# BACKPMAN20_CPU.net
KiCad netlist of a schematic drawn in Altium Designer
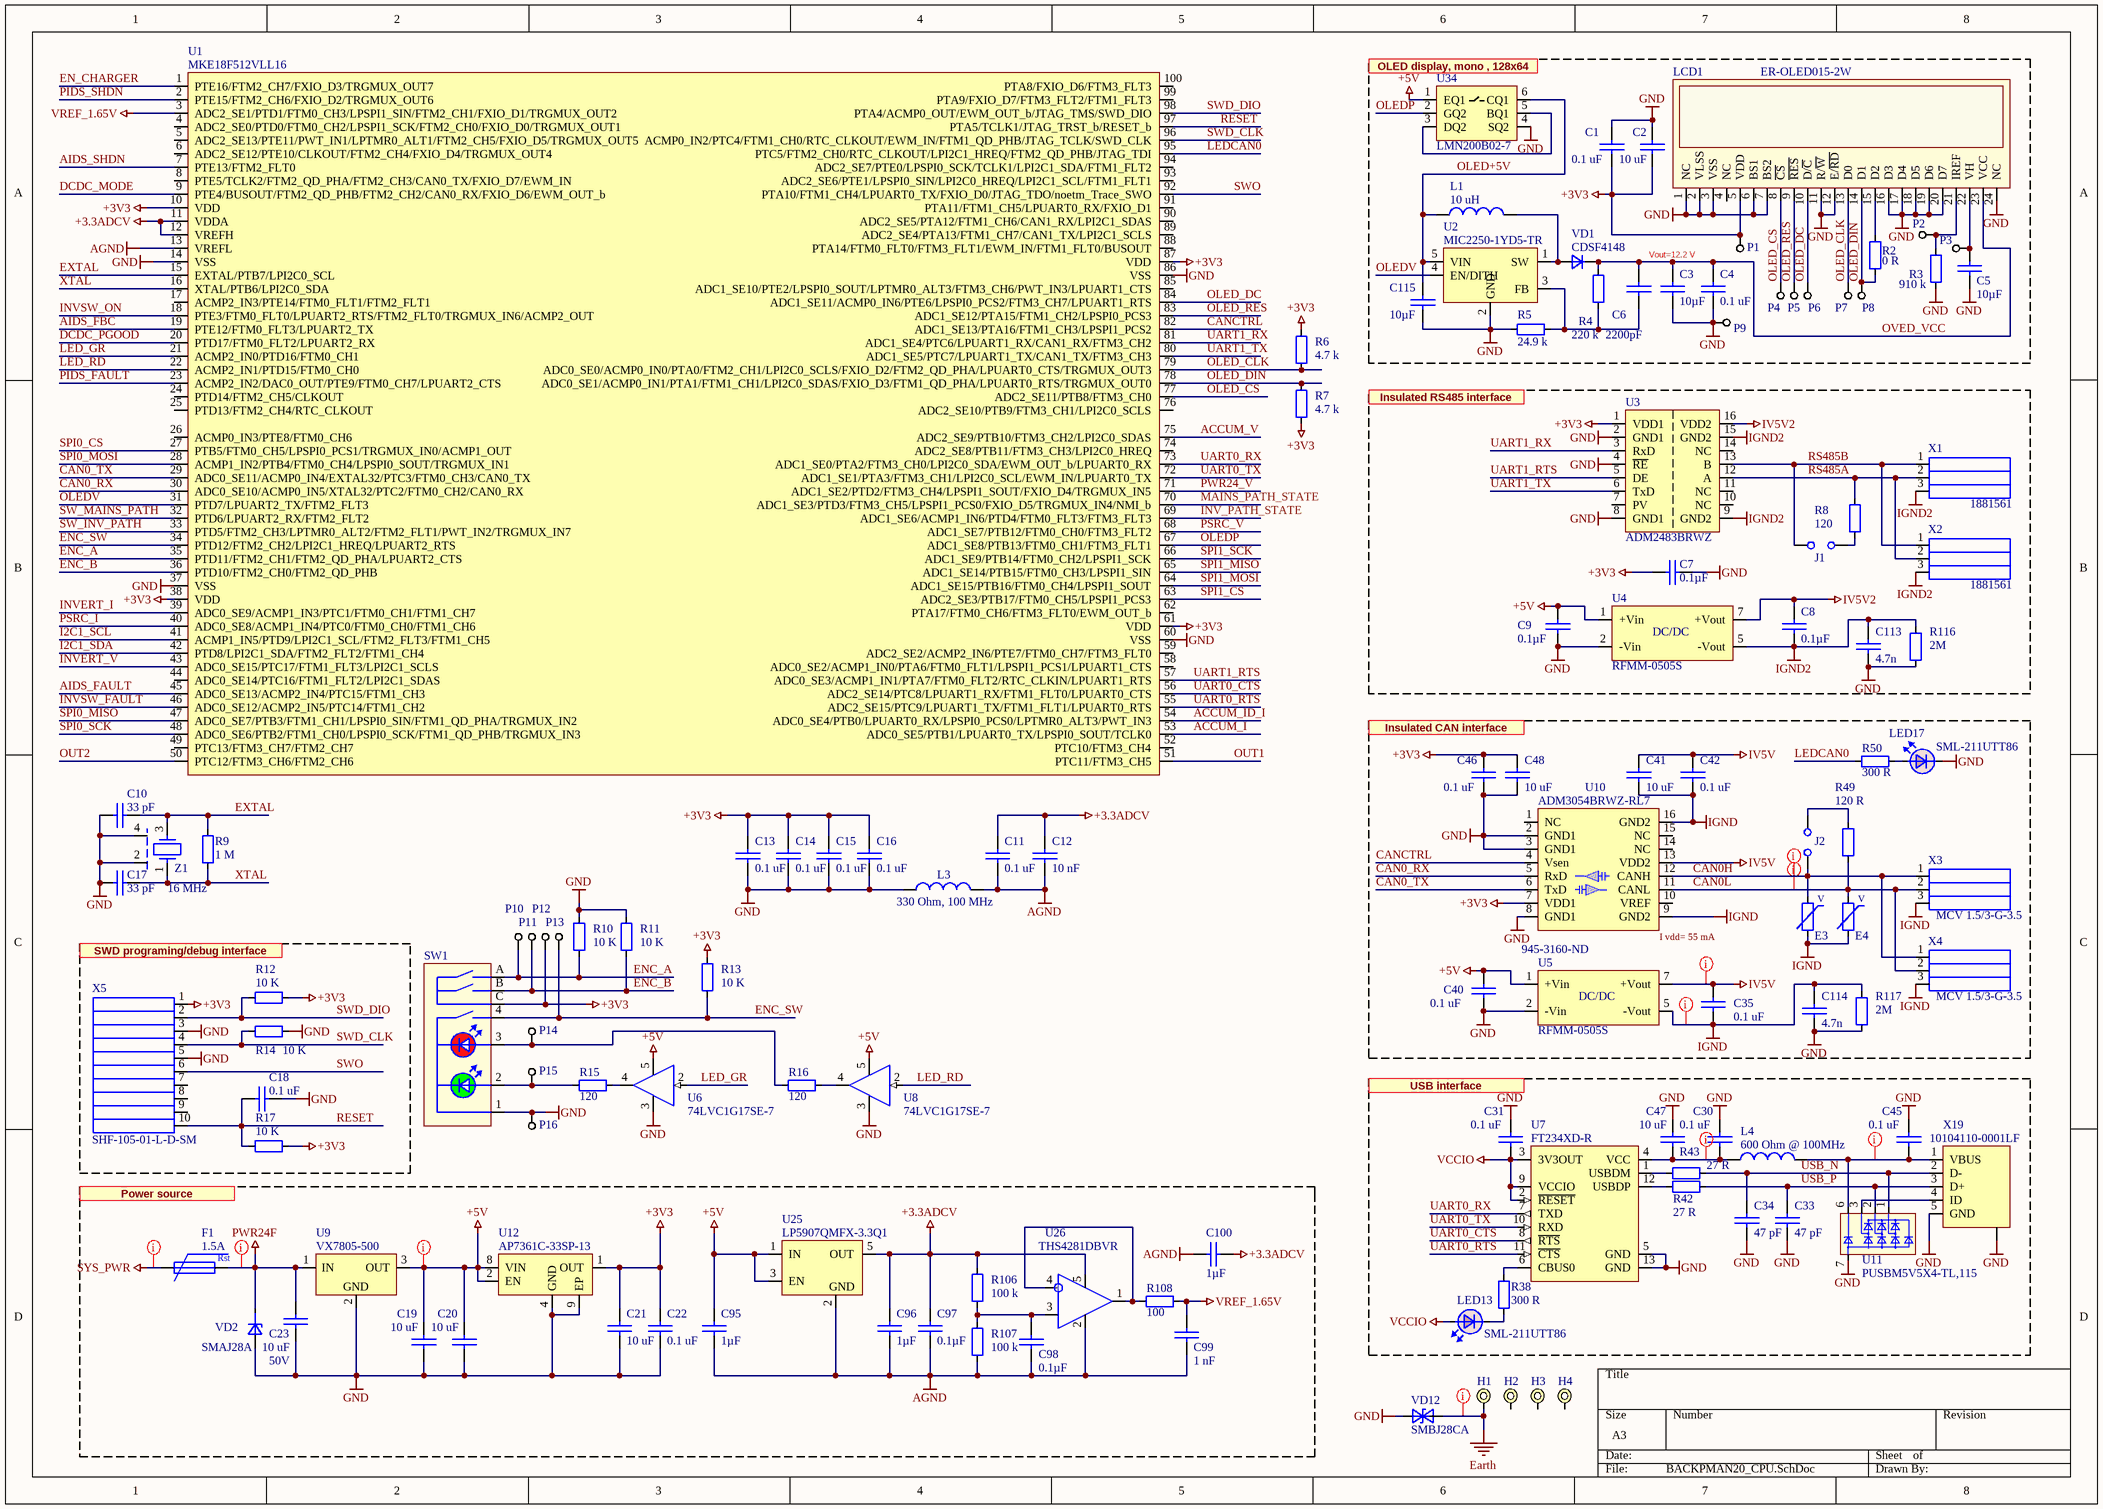
[diagram p0: BACKPMAN20_CPU.SchDoc]

(export (version "E")
  (design (tool "Eeschema 10.0.6"))
  (components
    (comp (ref "C1")
      (value "0.1 uF")
      (footprint "1608[0603]")
      (description "0.1 uF, 50V, 10% , X7R,  0603 SMD MLC Capacitor")
      (fields (field (name "TOLERANCE") "±10%") (field (name "MANUFACTURER") "WALSIN"))
      (libsource (lib "ea_Capacitors") (part "CVNF100K0603-25"))
    )
    (comp (ref "C2")
      (value "10 uF")
      (footprint "0805-1206")
      (description "CAP CER 10UF 10V 10% X5R 0805")
      (fields (field (name "MANUFACTURER") "Taiyo Yuden") (field (name "TOLERANCE") "10%"))
      (libsource (lib "ea_Capacitors") (part "LMK212F106ZG-T"))
    )
    (comp (ref "C3")
      (value "10µF")
      (footprint "0805 CAP")
      (description "10µF, ±10%, 25V, X5R, 0805 (2012 Metric), -55°C ~ 85°C, -, General Purpose")
      (fields (field (name "PART NUMBER") "TMK212BBJ106KG-T") (field (name "MANUFACTURER") "Taiyo Yuden"))
      (libsource (lib "ea_PassivComps") (part "Capacitor"))
    )
    (comp (ref "C4")
      (value "0.1 uF")
      (footprint "1608[0603]")
      (description "0.1 uF, 50V, 10% , X7R,  0603 SMD MLC Capacitor")
      (fields (field (name "TOLERANCE") "±10%") (field (name "MANUFACTURER") "WALSIN"))
      (libsource (lib "ea_Capacitors") (part "CVNF100K0603-25"))
    )
    (comp (ref "C5")
      (value "10µF")
      (footprint "0805 CAP")
      (description "10µF, ±10%, 25V, X5R, 0805 (2012 Metric), -55°C ~ 85°C, -, General Purpose")
      (fields (field (name "PART NUMBER") "TMK212BBJ106KG-T") (field (name "MANUFACTURER") "Taiyo Yuden"))
      (libsource (lib "ea_PassivComps") (part "Capacitor"))
    )
    (comp (ref "C6")
      (value "2200pF")
      (footprint "0603 CAP")
      (description "2200pF, ±10%, 25V, X7R, 0603 (1608 Metric), -55°C ~ 125°C, -, General Purpose")
      (fields (field (name "PART NUMBER") "CC0603KRX7R8BB222") (field (name "MANUFACTURER") "Yageo"))
      (libsource (lib "ea_PassivComps") (part "Capacitor"))
    )
    (comp (ref "C7")
      (value "0.1µF")
      (footprint "0603 CAP")
      (description "0.1µF, ±10%, 16V, X7R, 0603 (1608 Metric), -55°C ~ 125°C, -, General Purpose")
      (fields
        (field (name "PART NUMBER") "CL10B104KO8NNNC")
        (field (name "MANUFACTURER") "Samsung Electro-Mechanics")
      )
      (libsource (lib "ea_PassivComps") (part "Capacitor"))
    )
    (comp (ref "C8")
      (value "0.1µF")
      (footprint "0603 CAP")
      (description "0.1µF, ±10%, 16V, X7R, 0603 (1608 Metric), -55°C ~ 125°C, -, General Purpose")
      (fields
        (field (name "PART NUMBER") "CL10B104KO8NNNC")
        (field (name "MANUFACTURER") "Samsung Electro-Mechanics")
      )
      (libsource (lib "ea_PassivComps") (part "Capacitor"))
    )
    (comp (ref "C9")
      (value "0.1µF")
      (footprint "0603 CAP")
      (description "0.1µF, ±10%, 16V, X7R, 0603 (1608 Metric), -55°C ~ 125°C, -, General Purpose")
      (fields
        (field (name "PART NUMBER") "CL10B104KO8NNNC")
        (field (name "MANUFACTURER") "Samsung Electro-Mechanics")
      )
      (libsource (lib "ea_PassivComps") (part "Capacitor"))
    )
    (comp (ref "C10")
      (value "33 pF")
      (footprint "1005[0402]")
      (description "33 pF, 5%, 50V, C0G, NP0,  -55°C..125°C, 0402")
      (fields (field (name "TOLERANCE") "5%") (field (name "MANUFACTURER") "Kemet"))
      (libsource (lib "ea_Capacitors_0402") (part "CL05C330JB5NNNC"))
    )
    (comp (ref "C11")
      (value "0.1 uF")
      (footprint "1608[0603]")
      (description "0.1 uF, 50V, 10% , X7R,  0603 SMD MLC Capacitor")
      (fields (field (name "TOLERANCE") "±10%") (field (name "MANUFACTURER") "WALSIN"))
      (libsource (lib "ea_Capacitors") (part "CVNF100K0603-25"))
    )
    (comp (ref "C12")
      (value "10 nF")
      (footprint "1608[0603]")
      (description "10 nF, 50V, 10%, X7R, 0603 SMD MLC Capacitor")
      (fields (field (name "TOLERANCE") "±10%") (field (name "MANUFACTURER") "Murata Electronics"))
      (libsource (lib "ea_Capacitors") (part "CVNF010K0603"))
    )
    (comp (ref "C13")
      (value "0.1 uF")
      (footprint "1608[0603]")
      (description "0.1 uF, 50V, 10% , X7R,  0603 SMD MLC Capacitor")
      (fields (field (name "TOLERANCE") "±10%") (field (name "MANUFACTURER") "WALSIN"))
      (libsource (lib "ea_Capacitors") (part "CVNF100K0603-25"))
    )
    (comp (ref "C14")
      (value "0.1 uF")
      (footprint "1608[0603]")
      (description "0.1 uF, 50V, 10% , X7R,  0603 SMD MLC Capacitor")
      (fields (field (name "TOLERANCE") "±10%") (field (name "MANUFACTURER") "WALSIN"))
      (libsource (lib "ea_Capacitors") (part "CVNF100K0603-25"))
    )
    (comp (ref "C15")
      (value "0.1 uF")
      (footprint "1608[0603]")
      (description "0.1 uF, 50V, 10% , X7R,  0603 SMD MLC Capacitor")
      (fields (field (name "TOLERANCE") "±10%") (field (name "MANUFACTURER") "WALSIN"))
      (libsource (lib "ea_Capacitors") (part "CVNF100K0603-25"))
    )
    (comp (ref "C16")
      (value "0.1 uF")
      (footprint "1608[0603]")
      (description "0.1 uF, 50V, 10% , X7R,  0603 SMD MLC Capacitor")
      (fields (field (name "TOLERANCE") "±10%") (field (name "MANUFACTURER") "WALSIN"))
      (libsource (lib "ea_Capacitors") (part "CVNF100K0603-25"))
    )
    (comp (ref "C17")
      (value "33 pF")
      (footprint "1005[0402]")
      (description "33 pF, 5%, 50V, C0G, NP0,  -55°C..125°C, 0402")
      (fields (field (name "TOLERANCE") "5%") (field (name "MANUFACTURER") "Kemet"))
      (libsource (lib "ea_Capacitors_0402") (part "CL05C330JB5NNNC"))
    )
    (comp (ref "C18")
      (value "0.1 uF")
      (footprint "1608[0603]")
      (description "0.1 uF, 50V, 10% , X7R,  0603 SMD MLC Capacitor")
      (fields (field (name "TOLERANCE") "±10%") (field (name "MANUFACTURER") "WALSIN"))
      (libsource (lib "ea_Capacitors") (part "CVNF100K0603-25"))
    )
    (comp (ref "C19")
      (value "10 uF")
      (footprint "0805-1206")
      (description "CAP CER 10UF 10V 10% X5R 0805")
      (fields (field (name "MANUFACTURER") "Taiyo Yuden") (field (name "TOLERANCE") "10%"))
      (libsource (lib "ea_Capacitors") (part "LMK212F106ZG-T"))
    )
    (comp (ref "C20")
      (value "10 uF")
      (footprint "0805-1206")
      (description "CAP CER 10UF 10V 10% X5R 0805")
      (fields (field (name "MANUFACTURER") "Taiyo Yuden") (field (name "TOLERANCE") "10%"))
      (libsource (lib "ea_Capacitors") (part "LMK212F106ZG-T"))
    )
    (comp (ref "C21")
      (value "10 uF")
      (footprint "0805-1206")
      (description "CAP CER 10UF 10V 10% X5R 0805")
      (fields (field (name "MANUFACTURER") "Taiyo Yuden") (field (name "TOLERANCE") "10%"))
      (libsource (lib "ea_Capacitors") (part "LMK212F106ZG-T"))
    )
    (comp (ref "C22")
      (value "0.1 uF")
      (footprint "1608[0603]")
      (description "0.1 uF, 50V, 10% , X7R,  0603 SMD MLC Capacitor")
      (fields (field (name "TOLERANCE") "±10%") (field (name "MANUFACTURER") "WALSIN"))
      (libsource (lib "ea_Capacitors") (part "CVNF100K0603-25"))
    )
    (comp (ref "C23")
      (value "10 uF")
      (footprint "3225[1210]")
      (description "10uF, 50V, 20%, Y5V (F), 1210")
      (fields
        (field (name "MANUFACTURER") "Taiyo Yuden")
        (field (name "TOLERANCE") "20%")
        (field (name "VOLTAGE") "50V")
      )
      (libsource (lib "ea_Capacitors") (part "GRM32DF51H106ZA01L"))
    )
    (comp (ref "C30")
      (value "0.1 uF")
      (footprint "1608[0603]")
      (description "0.1 uF, 50V, 10% , X7R,  0603 SMD MLC Capacitor")
      (fields (field (name "TOLERANCE") "±10%") (field (name "MANUFACTURER") "WALSIN"))
      (libsource (lib "ea_Capacitors") (part "CVNF100K0603-25"))
    )
    (comp (ref "C31")
      (value "0.1 uF")
      (footprint "1608[0603]")
      (description "0.1 uF, 50V, 10% , X7R,  0603 SMD MLC Capacitor")
      (fields (field (name "TOLERANCE") "±10%") (field (name "MANUFACTURER") "WALSIN"))
      (libsource (lib "ea_Capacitors") (part "CVNF100K0603-25"))
    )
    (comp (ref "C33")
      (value "47 pF")
      (footprint "1608[0603]")
      (description "47 pF, 50V, 5%, NP0 SMD, -55°C ~ 150°C, 0603")
      (fields (field (name "MANUFACTURER") "TDK Corporation") (field (name "TOLERANCE") "5%"))
      (libsource (lib "ea_Capacitors_0603") (part "C1608NP01H470J080AA"))
    )
    (comp (ref "C34")
      (value "47 pF")
      (footprint "1608[0603]")
      (description "47 pF, 50V, 5%, NP0 SMD, -55°C ~ 150°C, 0603")
      (fields (field (name "MANUFACTURER") "TDK Corporation") (field (name "TOLERANCE") "5%"))
      (libsource (lib "ea_Capacitors_0603") (part "C1608NP01H470J080AA"))
    )
    (comp (ref "C35")
      (value "0.1 uF")
      (footprint "1608[0603]")
      (description "0.1 uF, 50V, 10% , X7R,  0603 SMD MLC Capacitor")
      (fields (field (name "TOLERANCE") "±10%") (field (name "MANUFACTURER") "WALSIN"))
      (libsource (lib "ea_Capacitors") (part "CVNF100K0603-25"))
    )
    (comp (ref "C40")
      (value "0.1 uF")
      (footprint "1608[0603]")
      (description "0.1 uF, 50V, 10% , X7R,  0603 SMD MLC Capacitor")
      (fields (field (name "TOLERANCE") "±10%") (field (name "MANUFACTURER") "WALSIN"))
      (libsource (lib "ea_Capacitors") (part "CVNF100K0603-25"))
    )
    (comp (ref "C41")
      (value "10 uF")
      (footprint "0805-1206")
      (description "CAP CER 10UF 10V 10% X5R 0805")
      (fields (field (name "MANUFACTURER") "Taiyo Yuden") (field (name "TOLERANCE") "10%"))
      (libsource (lib "ea_Capacitors") (part "LMK212F106ZG-T"))
    )
    (comp (ref "C42")
      (value "0.1 uF")
      (footprint "1608[0603]")
      (description "0.1 uF, 50V, 10% , X7R,  0603 SMD MLC Capacitor")
      (fields (field (name "TOLERANCE") "±10%") (field (name "MANUFACTURER") "WALSIN"))
      (libsource (lib "ea_Capacitors") (part "CVNF100K0603-25"))
    )
    (comp (ref "C45")
      (value "0.1 uF")
      (footprint "1608[0603]")
      (description "0.1 uF, 50V, 10% , X7R,  0603 SMD MLC Capacitor")
      (fields (field (name "TOLERANCE") "±10%") (field (name "MANUFACTURER") "WALSIN"))
      (libsource (lib "ea_Capacitors") (part "CVNF100K0603-25"))
    )
    (comp (ref "C46")
      (value "0.1 uF")
      (footprint "1608[0603]")
      (description "0.1 uF, 50V, 10% , X7R,  0603 SMD MLC Capacitor")
      (fields (field (name "TOLERANCE") "±10%") (field (name "MANUFACTURER") "WALSIN"))
      (libsource (lib "ea_Capacitors") (part "CVNF100K0603-25"))
    )
    (comp (ref "C47")
      (value "10 uF")
      (footprint "0805-1206")
      (description "10 uF, 6.3V, X5R, 10%, 0805")
      (fields (field (name "MANUFACTURER") "Murata") (field (name "TOLERANCE") "10%"))
      (libsource (lib "ea_Capacitors") (part "GRM21BR60J106KE19L"))
    )
    (comp (ref "C48")
      (value "10 uF")
      (footprint "0805-1206")
      (description "CAP CER 10UF 10V 10% X5R 0805")
      (fields (field (name "MANUFACTURER") "Taiyo Yuden") (field (name "TOLERANCE") "10%"))
      (libsource (lib "ea_Capacitors") (part "LMK212F106ZG-T"))
    )
    (comp (ref "C95")
      (value "1µF")
      (footprint "0603 CAP")
      (description "1µF, ±10%, 16V, X5R, 0603 (1608 Metric), -55°C ~ 85°C, -, General Purpose")
      (fields (field (name "PART NUMBER") "EMK107BJ105KA-T") (field (name "MANUFACTURER") "Taiyo Yuden"))
      (libsource (lib "ea_PassivComps") (part "Capacitor"))
    )
    (comp (ref "C96")
      (value "1µF")
      (footprint "0603 CAP")
      (description "1µF, ±10%, 16V, X5R, 0603 (1608 Metric), -55°C ~ 85°C, -, General Purpose")
      (fields (field (name "PART NUMBER") "EMK107BJ105KA-T") (field (name "MANUFACTURER") "Taiyo Yuden"))
      (libsource (lib "ea_PassivComps") (part "Capacitor"))
    )
    (comp (ref "C97")
      (value "0.1µF")
      (footprint "0603 CAP")
      (description "0.1µF, ±10%, 50V, X8L, 0603 (1608 Metric), -55°C ~ 150°C, -, Automotive")
      (fields
        (field (name "PART NUMBER") "GCM188L81H104KA57D")
        (field (name "MANUFACTURER") "Murata Electronics North America")
      )
      (libsource (lib "ea_PassivComps") (part "Capacitor"))
    )
    (comp (ref "C98")
      (value "0.1µF")
      (footprint "0603 CAP")
      (description "0.1µF, ±10%, 50V, X8L, 0603 (1608 Metric), -55°C ~ 150°C, -, Automotive")
      (fields
        (field (name "PART NUMBER") "GCM188L81H104KA57D")
        (field (name "MANUFACTURER") "Murata Electronics North America")
      )
      (libsource (lib "ea_PassivComps") (part "Capacitor"))
    )
    (comp (ref "C99")
      (value "1 nF")
      (footprint "0603 CAP")
      (description "1000pF, ±5%, 50V, X7R, 0603 (1608 Metric), -55°C ~ 125°C, -, General Purpose")
      (fields (field (name "PART NUMBER") "CC0603JRX7R9BB102") (field (name "MANUFACTURER") "Yageo"))
      (libsource (lib "ea_PassivComps") (part "Capacitor"))
    )
    (comp (ref "C100")
      (value "1µF")
      (footprint "0603 CAP")
      (description "1µF, ±10%, 16V, X5R, 0603 (1608 Metric), -55°C ~ 85°C, -, General Purpose")
      (fields (field (name "PART NUMBER") "EMK107BJ105KA-T") (field (name "MANUFACTURER") "Taiyo Yuden"))
      (libsource (lib "ea_PassivComps") (part "Capacitor"))
    )
    (comp (ref "C113")
      (value "4.7n")
      (footprint "0805 CAP")
      (description "4700pF ±10% 1000V (1kV) Ceramic Capacitor X7R 0805 (2012 Metric),-55°C ~ 125°C")
      (fields (field (name "MANUFACTURER") "KEMET") (field (name "TOLERANCE") "10%"))
      (libsource (lib "ea_Capacitors") (part "C0805V472KDRACTU"))
    )
    (comp (ref "C114")
      (value "4.7n")
      (footprint "0805 CAP")
      (description "4700pF ±10% 1000V (1kV) Ceramic Capacitor X7R 0805 (2012 Metric),-55°C ~ 125°C")
      (fields (field (name "MANUFACTURER") "KEMET") (field (name "TOLERANCE") "10%"))
      (libsource (lib "ea_Capacitors") (part "C0805V472KDRACTU"))
    )
    (comp (ref "C115")
      (value "10µF")
      (footprint "0805 CAP")
      (description "10µF, ±10%, 25V, X5R, 0805 (2012 Metric), -55°C ~ 85°C, -, General Purpose")
      (fields (field (name "PART NUMBER") "TMK212BBJ106KG-T") (field (name "MANUFACTURER") "Taiyo Yuden"))
      (libsource (lib "ea_PassivComps") (part "Capacitor"))
    )
    (comp (ref "E3")
      (value "823 560 505 60")
      (footprint "0603")
      (description "SUPPRESSOR ESD 5VDC, 56pF,  0603, -40..+85C")
      (fields (field (name "MANUFACTURER") "Würth Elektronik") (field (name "VOLTAGE") "5V"))
      (libsource (lib "ea_TVS_protection") (part "823 560 501 01"))
    )
    (comp (ref "E4")
      (value "823 560 505 60")
      (footprint "0603")
      (description "SUPPRESSOR ESD 5VDC, 56pF,  0603, -40..+85C")
      (fields (field (name "MANUFACTURER") "Würth Elektronik") (field (name "VOLTAGE") "5V"))
      (libsource (lib "ea_TVS_protection") (part "823 560 501 01"))
    )
    (comp (ref "F1")
      (value "1.5A")
      (footprint "2920 (7351 Metric)")
      (description "PTC RESETTABLE 60V 750MA, It=1.5A, 0.3s 2920(7351)")
      (fields (field (name "MANUFACTURER") "Bel Fuse Inc.") (field (name "PARTNUM") "507-1743-1-ND"))
      (libsource (lib "ea_Fuses") (part "0ZCF0075AF2C"))
    )
    (comp (ref "H1")
      (value "Hole 5MM Plated")
      (footprint "HOLE_5MM plated")
      (libsource (lib "ea_Mechanical") (part "Hole 5MM Plated"))
    )
    (comp (ref "H2")
      (value "Hole 5MM Plated")
      (footprint "HOLE_5MM plated")
      (libsource (lib "ea_Mechanical") (part "Hole 5MM Plated"))
    )
    (comp (ref "H3")
      (value "Hole 5MM Plated")
      (footprint "HOLE_5MM plated")
      (libsource (lib "ea_Mechanical") (part "Hole 5MM Plated"))
    )
    (comp (ref "H4")
      (value "Hole 5MM Plated")
      (footprint "HOLE_5MM plated")
      (libsource (lib "ea_Mechanical") (part "Hole 5MM Plated"))
    )
    (comp (ref "J1")
      (value "PH1-02-TA-HT")
      (footprint "HDR1X2V")
      (description "2 Pos. 2.54 mm Single Row Through Hole Straight Pin Header")
      (fields (field (name "MANUFACTURER") "ADAM TECH"))
      (libsource (lib "ea_Commutation") (part "Jumper"))
    )
    (comp (ref "J2")
      (value "PH1-02-TA-HT")
      (footprint "HDR1X2V")
      (description "2 Pos. 2.54 mm Single Row Through Hole Straight Pin Header")
      (fields (field (name "MANUFACTURER") "ADAM TECH"))
      (libsource (lib "ea_Commutation") (part "Jumper"))
    )
    (comp (ref "L1")
      (value "10 uH")
      (footprint "VLS4012ET")
      (description "10uH, 890 mA, 0.228 Ohm, +-20%,- 40 C to + 105 C")
      (fields (field (name "MANUFACTURER") "TDK Corporation") (field (name "PARTNUM") "445-6681-1-ND"))
      (libsource (lib "ea_Inductors") (part "VLS4012ET-100M"))
    )
    (comp (ref "L3")
      (value "330 Ohm, 100 MHz")
      (footprint "0603")
      (description "Ferrite bead, 330 Ohm, 100 MHz,  1.5 A, 0.07 Ohm")
      (fields
        (field (name "MANUFACTURER") "Murata Electronics North America")
        (field (name "PARTNUM") "BLM18SG331TN1D")
      )
      (libsource (lib "*") (part "BLM18SG331TN1D"))
    )
    (comp (ref "L4")
      (value "600 Ohm @ 100MHz")
      (footprint "0805")
      (description "FERRITE BEAD 600 OHM, 0805, -55°C ~ 125°C")
      (fields (field (name "MANUFACTURER") "TDK Corporation") (field (name "PARTNUM") "445-2206-1-ND"))
      (libsource (lib "ea_Inductors") (part "MPZ2012S601AT000"))
    )
    (comp (ref "LCD1")
      (value "ER-OLED015-2W")
      (footprint "ER-OLED015-2")
      (description "1.5\"OLED Display Serial 128x64 Module,SSD1309,White on Black")
      (fields
        (field (name "MANUFACTURER") "Orient Display")
        (field (name "PARTNUM") "2544-AOM12864A0-1.54WW-ND")
      )
      (libsource (lib "ea_LCD") (part "ER-OLED015-2W"))
    )
    (comp (ref "LED13")
      (value "SML-211UTT86")
      (footprint "0805 LED")
      (description "0805 red LED, hibright, 2 mA, 1.8V, 130°")
      (fields (field (name "MANUFACTURER") "Rohm") (field (name "PARTNUM") "511-1292-1-ND"))
      (libsource (lib "ea_Indicators") (part "SML-211UTT86"))
    )
    (comp (ref "LED17")
      (value "SML-211UTT86")
      (footprint "0805 LED")
      (description "0805 red LED, hibright, 2 mA, 1.8V, 130°")
      (fields (field (name "MANUFACTURER") "Rohm") (field (name "PARTNUM") "511-1292-1-ND"))
      (libsource (lib "ea_Indicators") (part "SML-211UTT86"))
    )
    (comp (ref "P1")
      (value "Pin 0.9 mm")
      (footprint "Pin 0.9 mm")
      (libsource (lib "ea_Contacts") (part "Pin 0.9 mm"))
    )
    (comp (ref "P2")
      (value "Pin 0.9 mm")
      (footprint "Pin 0.9 mm")
      (libsource (lib "ea_Contacts") (part "Pin 0.9 mm"))
    )
    (comp (ref "P3")
      (value "Pin 0.9 mm")
      (footprint "Pin 0.9 mm")
      (libsource (lib "ea_Contacts") (part "Pin 0.9 mm"))
    )
    (comp (ref "P4")
      (value "Pin 0.9 mm")
      (footprint "Pin 0.9 mm")
      (libsource (lib "ea_Contacts") (part "Pin 0.9 mm"))
    )
    (comp (ref "P5")
      (value "Pin 0.9 mm")
      (footprint "Pin 0.9 mm")
      (libsource (lib "ea_Contacts") (part "Pin 0.9 mm"))
    )
    (comp (ref "P6")
      (value "Pin 0.9 mm")
      (footprint "Pin 0.9 mm")
      (libsource (lib "ea_Contacts") (part "Pin 0.9 mm"))
    )
    (comp (ref "P7")
      (value "Pin 0.9 mm")
      (footprint "Pin 0.9 mm")
      (libsource (lib "ea_Contacts") (part "Pin 0.9 mm"))
    )
    (comp (ref "P8")
      (value "Pin 0.9 mm")
      (footprint "Pin 0.9 mm")
      (libsource (lib "ea_Contacts") (part "Pin 0.9 mm"))
    )
    (comp (ref "P9")
      (value "Pin 0.9 mm")
      (footprint "Pin 0.9 mm")
      (libsource (lib "ea_Contacts") (part "Pin 0.9 mm"))
    )
    (comp (ref "P10")
      (value "Pin 0.9 mm")
      (footprint "Pin 0.9 mm")
      (libsource (lib "ea_Contacts") (part "Pin 0.9 mm"))
    )
    (comp (ref "P11")
      (value "Pin 0.9 mm")
      (footprint "Pin 0.9 mm")
      (libsource (lib "ea_Contacts") (part "Pin 0.9 mm"))
    )
    (comp (ref "P12")
      (value "Pin 0.9 mm")
      (footprint "Pin 0.9 mm")
      (libsource (lib "ea_Contacts") (part "Pin 0.9 mm"))
    )
    (comp (ref "P13")
      (value "Pin 0.9 mm")
      (footprint "Pin 0.9 mm")
      (libsource (lib "ea_Contacts") (part "Pin 0.9 mm"))
    )
    (comp (ref "P14")
      (value "Pin 0.9 mm")
      (footprint "Pin 0.9 mm")
      (libsource (lib "ea_Contacts") (part "Pin 0.9 mm"))
    )
    (comp (ref "P15")
      (value "Pin 0.9 mm")
      (footprint "Pin 0.9 mm")
      (libsource (lib "ea_Contacts") (part "Pin 0.9 mm"))
    )
    (comp (ref "P16")
      (value "Pin 0.9 mm")
      (footprint "Pin 0.9 mm")
      (libsource (lib "ea_Contacts") (part "Pin 0.9 mm"))
    )
    (comp (ref "R2")
      (value "0 R")
      (footprint "0603")
      (description "0 R, Jumper, 0603, SMD Resistor, -55°C ~ 155°C")
      (fields (field (name "MANUFACTURER") "Yageo") (field (name "VOLTAGE") "75 V"))
      (libsource (lib "ea_Resistors_0603") (part "RC0603FR-070RL"))
    )
    (comp (ref "R3")
      (value "910 k")
      (footprint "0603")
      (fields
        (field (name "MANUFACTURER") "Stackpole Electronics Inc.")
        (field (name "TOLERANCE") "±1%")
        (field (name "VOLTAGE") "75V")
      )
      (libsource (lib "") (part "Resistor_1"))
    )
    (comp (ref "R4")
      (value "220 k")
      (footprint "0603")
      (fields
        (field (name "MANUFACTURER") "Stackpole Electronics Inc.")
        (field (name "TOLERANCE") "±1%")
        (field (name "VOLTAGE") "75V")
      )
      (libsource (lib "") (part "Resistor_1"))
    )
    (comp (ref "R5")
      (value "24.9 k")
      (footprint "0603")
      (fields
        (field (name "MANUFACTURER") "Stackpole Electronics Inc.")
        (field (name "TOLERANCE") "±1%")
        (field (name "VOLTAGE") "75V")
      )
      (libsource (lib "ea_PassivComps") (part "Resistor"))
    )
    (comp (ref "R6")
      (value "4.7 k")
      (footprint "0603")
      (fields
        (field (name "MANUFACTURER") "Stackpole Electronics Inc.")
        (field (name "TOLERANCE") "±1%")
        (field (name "VOLTAGE") "75V")
      )
      (libsource (lib "") (part "Resistor_1"))
    )
    (comp (ref "R7")
      (value "4.7 k")
      (footprint "0603")
      (fields
        (field (name "MANUFACTURER") "Stackpole Electronics Inc.")
        (field (name "TOLERANCE") "±1%")
        (field (name "VOLTAGE") "75V")
      )
      (libsource (lib "") (part "Resistor_1"))
    )
    (comp (ref "R8")
      (value "120")
      (footprint "0603")
      (fields
        (field (name "MANUFACTURER") "Stackpole Electronics Inc.")
        (field (name "TOLERANCE") "±1%")
        (field (name "VOLTAGE") "75V")
      )
      (libsource (lib "") (part "Resistor_1"))
    )
    (comp (ref "R9")
      (value "1 M")
      (footprint "0402")
      (description "1 M,  ±1%, ±100ppm/°C, Thick Film, -55°C ~ 155°C, 0402")
      (fields (field (name "MANUFACTURER") "Yageo") (field (name "TOLERANCE") "1%"))
      (libsource (lib "ea_Resistors_0402") (part "RC0402FR-071ML"))
    )
    (comp (ref "R10")
      (value "10 K")
      (footprint "0603")
      (description "10 K, 1%, 0603, SMD Resistor, Taped")
      (fields (field (name "MANUFACTURER") "Vishay") (field (name "TOLERANCE") "1%"))
      (libsource (lib "ea_Resistors_0603") (part "RL0603K010-1"))
    )
    (comp (ref "R11")
      (value "10 K")
      (footprint "0603")
      (description "10 K, 1%, 0603, SMD Resistor, Taped")
      (fields (field (name "MANUFACTURER") "Vishay") (field (name "TOLERANCE") "1%"))
      (libsource (lib "ea_Resistors_0603") (part "RL0603K010-1"))
    )
    (comp (ref "R12")
      (value "10 K")
      (footprint "0603")
      (description "10 K, 1%, 0603, SMD Resistor, Taped")
      (fields (field (name "MANUFACTURER") "Vishay") (field (name "TOLERANCE") "1%"))
      (libsource (lib "") (part "RL0603K010-1_1"))
    )
    (comp (ref "R13")
      (value "10 K")
      (footprint "0603")
      (description "10 K, 1%, 0603, SMD Resistor, Taped")
      (fields (field (name "MANUFACTURER") "Vishay") (field (name "TOLERANCE") "1%"))
      (libsource (lib "ea_Resistors_0603") (part "RL0603K010-1"))
    )
    (comp (ref "R14")
      (value "10 K")
      (footprint "0603")
      (description "10 K, 1%, 0603, SMD Resistor, Taped")
      (fields (field (name "MANUFACTURER") "Vishay") (field (name "TOLERANCE") "1%"))
      (libsource (lib "") (part "RL0603K010-1_1"))
    )
    (comp (ref "R15")
      (value "120")
      (footprint "0603")
      (fields
        (field (name "MANUFACTURER") "Stackpole Electronics Inc.")
        (field (name "TOLERANCE") "±1%")
        (field (name "VOLTAGE") "75V")
      )
      (libsource (lib "ea_PassivComps") (part "Resistor"))
    )
    (comp (ref "R16")
      (value "120")
      (footprint "0603")
      (fields
        (field (name "MANUFACTURER") "Stackpole Electronics Inc.")
        (field (name "TOLERANCE") "±1%")
        (field (name "VOLTAGE") "75V")
      )
      (libsource (lib "ea_PassivComps") (part "Resistor"))
    )
    (comp (ref "R17")
      (value "10 K")
      (footprint "0603")
      (description "10 K, 1%, 0603, SMD Resistor, Taped")
      (fields (field (name "MANUFACTURER") "Vishay") (field (name "TOLERANCE") "1%"))
      (libsource (lib "") (part "RL0603K010-1_1"))
    )
    (comp (ref "R38")
      (value "300 R")
      (footprint "0603")
      (description "300 R, 1%, 0.1 W, 0603, SMD Resistor, Taped")
      (fields (field (name "MANUFACTURER") "Vishay/Dale") (field (name "TOLERANCE") "1%"))
      (libsource (lib "") (part "CRCW0603300RFKEA_1"))
    )
    (comp (ref "R42")
      (value "27 R")
      (footprint "0603")
      (description "27 R, 1%, 0603, SMD,  -55°C ~ 155°C")
      (fields (field (name "MANUFACTURER") "Yageo") (field (name "TOLERANCE") "1%"))
      (libsource (lib "ea_Resistors_0603") (part "RC0603FR-0727RL"))
    )
    (comp (ref "R43")
      (value "27 R")
      (footprint "0603")
      (description "27 R, 1%, 0603, SMD,  -55°C ~ 155°C")
      (fields (field (name "MANUFACTURER") "Yageo") (field (name "TOLERANCE") "1%"))
      (libsource (lib "ea_Resistors_0603") (part "RC0603FR-0727RL"))
    )
    (comp (ref "R49")
      (value "120 R")
      (footprint "0603")
      (description "120 R, 1%, 0603, SMD Resistor, Taped")
      (fields (field (name "MANUFACTURER") "Vishay") (field (name "TOLERANCE") "±1%"))
      (libsource (lib "ea_Resistors") (part "RL0603E120-1"))
    )
    (comp (ref "R50")
      (value "300 R")
      (footprint "0603")
      (description "300 R, 1%, 0.1 W, 0603, SMD Resistor, Taped")
      (fields (field (name "MANUFACTURER") "Vishay/Dale") (field (name "TOLERANCE") "1%"))
      (libsource (lib "ea_Resistors_0603") (part "CRCW0603300RFKEA"))
    )
    (comp (ref "R106")
      (value "100 k")
      (footprint "0603")
      (description "100 kOhms, ±0.1%, 0.1W, 1/10W, Thin Film, ±25ppm/°C, 0603 (1608 Metric), -55°C ~ 155°C, -")
      (fields (field (name "MANUFACTURER") "Yageo") (field (name "TOLERANCE") "±0.1%"))
      (libsource (lib "") (part "Resistor_1"))
    )
    (comp (ref "R107")
      (value "100 k")
      (footprint "0603")
      (description "100 kOhms, ±0.1%, 0.1W, 1/10W, Thin Film, ±25ppm/°C, 0603 (1608 Metric), -55°C ~ 155°C, -")
      (fields (field (name "MANUFACTURER") "Yageo") (field (name "TOLERANCE") "±0.1%"))
      (libsource (lib "") (part "Resistor_1"))
    )
    (comp (ref "R108")
      (value "100")
      (footprint "0603")
      (fields
        (field (name "MANUFACTURER") "Stackpole Electronics Inc.")
        (field (name "TOLERANCE") "±1%")
        (field (name "VOLTAGE") "75V")
      )
      (libsource (lib "ea_PassivComps") (part "Resistor"))
    )
    (comp (ref "R116")
      (value "2M")
      (footprint "1206")
      (description "2 MOhms ±1% 0.25W, 1/4W Chip Resistor 1206 (3216 Metric) High Voltage Thick Film,-55°C ~ 155°C")
      (fields (field (name "MANUFACTURER") "Vishay Dale") (field (name "TOLERANCE") "±1%"))
      (libsource (lib "ea_Resistors") (part "RCV12062M00FKEA"))
    )
    (comp (ref "R117")
      (value "2M")
      (footprint "1206")
      (description "2 MOhms ±1% 0.25W, 1/4W Chip Resistor 1206 (3216 Metric) High Voltage Thick Film,-55°C ~ 155°C")
      (fields (field (name "MANUFACTURER") "Vishay Dale") (field (name "TOLERANCE") "±1%"))
      (libsource (lib "ea_Resistors") (part "RCV12062M00FKEA"))
    )
    (comp (ref "SW1")
      (value "PEL12D-4225S-S2024")
      (footprint "PEL12D-4225S-S2024")
      (description "Rotary Encoder Mechanical 24 Quadrature (Incremental) Vertical")
      (fields (field (name "MANUFACTURER") "Bourns Inc.") (field (name "PARTNUM") "PEL12D-4225S-S2024-ND"))
      (libsource (lib "ea_Commutation") (part "PEL12D-4225S-S2024"))
    )
    (comp (ref "U1")
      (value "MKE18F512VLL16")
      (footprint "LQPF100")
      (fields (field (name "MANUFACTURER") "NXP USA Inc.") (field (name "PARTNUM") "MKE18F512VLL16-ND"))
      (libsource (lib "ea_IC_CPU") (part "MKE18F512VLL16"))
    )
    (comp (ref "U2")
      (value "MIC2250-1YD5-TR")
      (footprint "SOT23-5")
      (description "Boost DC/DC, 2.5..5.5 to 1.24..32V, 900vA, 2.5Mhz, SOT-23-5, -40..+125 C")
      (fields (field (name "PARTNUM") "576-3967-1-ND") (field (name "MANUFACTURER") "Microchip Technology"))
      (libsource (lib "ea_IC_Power_Reg_Ref_Sw") (part "MIC2250-1YD5-TR"))
    )
    (comp (ref "U3")
      (value "ADM2483BRWZ")
      (footprint "SO-G16/D10.4")
      (description "RS422, RS485 Digital Isolator 2500Vrms 3 Channel 500kbps 25kV/µs CMTI 16-SOIC, -40°C ~ 85°C")
      (fields (field (name "MANUFACTURER") "Analog Divices") (field (name "PARTNUM") "ADM2483BRWZ-ND"))
      (libsource (lib "ea_IC_Interfaces") (part "ADM2483BRWZ"))
    )
    (comp (ref "U4")
      (value "RFMM-0505S")
      (footprint "Recom 7-SIP module")
      (description "1W DC-DC Unregulated Single Output , 5V in, 5 V out,  200mA, 4 kV, -40°C ~ 85°C")
      (fields (field (name "MANUFACTURER") "Recom Power") (field (name "PARTNUM") "945-3160-ND"))
      (libsource (lib "ea_PowerSources") (part "RFMM-0505S"))
    )
    (comp (ref "U5")
      (value "RFMM-0505S")
      (footprint "Recom 7-SIP module")
      (description "1W DC-DC Unregulated Single Output , 5V in, 5 V out,  200mA, 4 kV, -40°C ~ 85°C")
      (fields
        (field (name "MANUFACTURER") "Recom Power")
        (field (name "PARTNUM") "945-3160-ND")
        (field (name "SUPPLIER PART NUMBER 1") "945-3160-ND")
      )
      (libsource (lib "ea_PowerSources") (part "RFMM-0505S"))
    )
    (comp (ref "U6")
      (value "74LVC1G17SE-7")
      (footprint "SOT-353 ON Semi")
      (description "IC SGL SCHMITT BUFFER SOT353")
      (fields
        (field (name "MANUFACTURER") "Diodes Incorporated")
        (field (name "PARTNUM") "74LVC1G17SE-7CT-ND")
      )
      (libsource (lib "ea_IC_Logic") (part "74LVC1G17SE-7"))
    )
    (comp (ref "U7")
      (value "FT234XD-R")
      (footprint "FTDI DFN-12")
      (description "USB Bridge, USB to UART USB 2.0 UART Interface 12-DFN (3x3)")
      (fields (field (name "MANUFACTURER") "FTDI") (field (name "PARTNUM") "768-1178-1-ND"))
      (libsource (lib "ea_IC_Interfaces") (part "FT234XD"))
    )
    (comp (ref "U8")
      (value "74LVC1G17SE-7")
      (footprint "SOT-353 ON Semi")
      (description "IC SGL SCHMITT BUFFER SOT353")
      (fields
        (field (name "MANUFACTURER") "Diodes Incorporated")
        (field (name "PARTNUM") "74LVC1G17SE-7CT-ND")
      )
      (libsource (lib "ea_IC_Logic") (part "74LVC1G17SE-7"))
    )
    (comp (ref "U9")
      (value "VX7805-500")
      (footprint "VX7805-500")
      (description "Linear Regulator Replacement DC DC Converter 1 Output 5V 500mA 6.5V - 36V Input")
      (fields (field (name "MANUFACTURER") "CUI Inc.") (field (name "PARTNUM") "102-4244-ND"))
      (libsource (lib "ea_IC_Power_Reg_Ref_Sw") (part "VX7805-500"))
    )
    (comp (ref "U10")
      (value "ADM3054BRWZ-RL7")
      (footprint "SO-G16/D10.4")
      (description "IC Isol TXRX CAN HS 16SOIC")
      (fields (field (name "MANUFACTURER") "Analog Divices") (field (name "PARTNUM") "ADM3054BRWZ-RL7CT-ND"))
      (libsource (lib "ea_IC_Interfaces") (part "ADM3054BRWZ-RL7"))
    )
    (comp (ref "U11")
      (value "PUSBM5V5X4-TL,115")
      (footprint "DFN1616-6")
      (description "TVS DIODE 5.5VWM 12VC 6HXSON")
      (fields (field (name "MANUFACTURER") "NXP Semiconductors") (field (name "PARTNUM") "568-10921-1-ND"))
      (libsource (lib "ea_TVS_protection") (part "PUSBM5V5X4-TL,115"))
    )
    (comp (ref "U12")
      (value "AP7361C-33SP-13")
      (footprint "SOIC-8 EDP")
      (description "LDO, 3.3 V, 1A, 0.36V@1A, Vin=6V max, -40..+85C, 8-SO-EP")
      (fields
        (field (name "PARTNUM") "AP7361C-33SP-13DICT-ND")
        (field (name "MANUFACTURER") "Diodes Incorporated")
      )
      (libsource (lib "ea_IC_Power_Reg_Ref_Sw") (part "AP7361C-33SP-13"))
    )
    (comp (ref "U25")
      (value "LP5907QMFX-3.3Q1")
      (footprint "SOT23-5")
      (description "LDO 3.3 V, 250 mA, Vin < 5.5V, Iq < 12uA, -40..+125 C, SOT23-5")
      (fields (field (name "MANUFACTURER") "Texas Instruments") (field (name "PARTNUM") "296-40365-1-ND"))
      (libsource (lib "ea_IC_Power_Reg_Ref_Sw") (part "LP5907QMFX-3.3Q1"))
    )
    (comp (ref "U26")
      (value "THS4281DBVR")
      (footprint "SOT23-5")
      (description "Voltage Feedback Amplifier 1 Circuit Rail-to-Rail SOT-23-5")
      (fields (field (name "MANUFACTURER") "Texas Instruments") (field (name "PARTNUM") "296-39224-1-ND"))
      (libsource (lib "ea_IC_OPAmps_AnComparators") (part "THS4281DBVR"))
    )
    (comp (ref "U34")
      (value "LMN200B02-7")
      (footprint "SOT363")
      (fields (field (name "MANUFACTURER") "Diodes Incorporated") (field (name "PARTNUM") "LMN200B02DICT-ND"))
      (libsource (lib "ea_IC_drivers") (part "LMN200B02-7"))
    )
    (comp (ref "VD1")
      (value "CDSF4148")
      (footprint "1005")
      (description "150 mA, 75V, 1005, 125 C")
      (fields (field (name "MANUFACTURER") "Comchip Technology") (field (name "PARTNUM") "641-1004-1-ND"))
      (libsource (lib "ea_Diodes") (part "CDSF4148"))
    )
    (comp (ref "VD2")
      (value "SMAJ28A")
      (footprint "SMA")
      (description "DIODE TVS 28V 400W UNI 5% SMD")
      (fields (field (name "MANUFACTURER") "Bourns Inc.") (field (name "PARTNUM") "SMAJ28ABCT-ND"))
      (libsource (lib "ea_TVS_protection") (part "SMAJ28A"))
    )
    (comp (ref "VD12")
      (value "SMBJ28CA")
      (footprint "DO-214AA_SMBJ BI")
      (description "TVS 600W 28V Bidirectional")
      (fields (field (name "MANUFACTURER") "Littelfuse") (field (name "PARTNUM") "SMBJ28CABCT-ND"))
      (libsource (lib "ea_TVS_protection") (part "SMBJ28CA"))
    )
    (comp (ref "X1")
      (value "1881561")
      (footprint "1881561")
      (description "Printed-circuit board connector - MCV 0,5/ 3-G-2,5 - 1881561")
      (fields (field (name "MANUFACTURER") "Phoenix Contact"))
      (libsource (lib "ea_Connectors_2.5_mm_pitch") (part "1881561"))
    )
    (comp (ref "X2")
      (value "1881561")
      (footprint "1881561")
      (description "Printed-circuit board connector - MCV 0,5/ 3-G-2,5 - 1881561")
      (fields (field (name "MANUFACTURER") "Phoenix Contact"))
      (libsource (lib "ea_Connectors_2.5_mm_pitch") (part "1881561"))
    )
    (comp (ref "X3")
      (value "MCV 1.5/3-G-3.5")
      (footprint "mcv1.5-3-g_3.5 green + MC 1,5 3-ST-3,5 - 1840379")
      (description "HEADER, VERTICAL, 3.5MM, 3WAY")
      (fields (field (name "MANUFACTURER") "PHOENIX CONTACT") (field (name "PARTNUM") "1843619"))
      (libsource (lib "ea_PhoenixContacts") (part "MCV 1.5/3-G-3.5"))
    )
    (comp (ref "X4")
      (value "MCV 1.5/3-G-3.5")
      (footprint "mcv1.5-3-g_3.5 green + MC 1,5 3-ST-3,5 - 1840379")
      (description "HEADER, VERTICAL, 3.5MM, 3WAY")
      (fields (field (name "MANUFACTURER") "PHOENIX CONTACT") (field (name "PARTNUM") "1843619"))
      (libsource (lib "ea_PhoenixContacts") (part "MCV 1.5/3-G-3.5"))
    )
    (comp (ref "X5")
      (value "SHF-105-01-L-D-SM")
      (footprint "SHF-105-01-L-D-SM")
      (description "10 Positions Header Connector 0.050\" (1.27mm) Surface Mount Gold")
      (fields (field (name "MANUFACTURER") "Samtec Inc."))
      (libsource (lib "ea_Connectors_1.27_mm_pitch") (part "SHF-105-01-L-D-SM"))
    )
    (comp (ref "X19")
      (value "10104110-0001LF")
      (footprint "FCI micro USB B receptacle SMD")
      (description "USB - micro B USB 2.0 Receptacle Connector 5 Position Surface Mount, Right Angle")
      (fields (field (name "MANUFACTURER") "Amphenol FCI") (field (name "PARTNUM") "609-4052-1-ND"))
      (libsource (lib "ea_Connectors_USB") (part "10104110-0001LF"))
    )
    (comp (ref "Z1")
      (value "16 MHz")
      (footprint "4-SMD 2.00mm x 1.60mm")
      (description "16 MHz, 9 pF, ±10ppm, 2.00mm x 1.60mm, -20°C ~ 70°C")
      (fields (field (name "MANUFACTURER") "Abracon LLC") (field (name "PARTNUM") "535-13598-1-ND"))
      (libsource (lib "ea_OSC_CLK_GEN") (part "ABM11-16.000MHZ-9-B1U-T"))
    )
  )
  (nets
    (net (code "1") (name "+3.3ADCV") (class "Default")
      (node (ref "C100") (pin "1") (pinfunction "1_1") (pintype "passive"))
      (node (ref "C11") (pin "2") (pinfunction "2_2") (pintype "passive"))
      (node (ref "C12") (pin "1") (pinfunction "1_1") (pintype "passive"))
      (node (ref "C96") (pin "2") (pinfunction "2_2") (pintype "passive"))
      (node (ref "C97") (pin "1") (pinfunction "1_1") (pintype "passive"))
      (node (ref "R106") (pin "2") (pinfunction "2_2") (pintype "passive"))
      (node (ref "U1") (pin "11") (pinfunction "VDDA_11") (pintype "power_in"))
      (node (ref "U1") (pin "12") (pinfunction "VREFH_12") (pintype "power_in"))
      (node (ref "U25") (pin "5") (pinfunction "OUT_5") (pintype "power_in"))
      (node (ref "U26") (pin "5") (pinfunction "V+_5") (pintype "power_in"))
    )
    (net (code "2") (name "+3V3") (class "Default")
      (node (ref "C1") (pin "2") (pinfunction "2_2") (pintype "passive"))
      (node (ref "C13") (pin "2") (pinfunction "2_2") (pintype "passive"))
      (node (ref "C14") (pin "2") (pinfunction "2_2") (pintype "passive"))
      (node (ref "C15") (pin "2") (pinfunction "2_2") (pintype "passive"))
      (node (ref "C16") (pin "2") (pinfunction "2_2") (pintype "passive"))
      (node (ref "C2") (pin "1") (pinfunction "1_1") (pintype "passive"))
      (node (ref "C21") (pin "2") (pinfunction "2_2") (pintype "passive"))
      (node (ref "C22") (pin "2") (pinfunction "2_2") (pintype "passive"))
      (node (ref "C46") (pin "2") (pinfunction "2_2") (pintype "passive"))
      (node (ref "C48") (pin "2") (pinfunction "2_2") (pintype "passive"))
      (node (ref "C7") (pin "1") (pinfunction "1_1") (pintype "passive"))
      (node (ref "LCD1") (pin "5") (pinfunction "VDD_5") (pintype "passive"))
      (node (ref "P1") (pin "1") (pinfunction "1_1") (pintype "passive"))
      (node (ref "P12") (pin "1") (pinfunction "1_1") (pintype "passive"))
      (node (ref "R12") (pin "2") (pinfunction "2_2") (pintype "passive"))
      (node (ref "R13") (pin "2") (pinfunction "2_2") (pintype "passive"))
      (node (ref "R17") (pin "2") (pinfunction "2_2") (pintype "passive"))
      (node (ref "R6") (pin "2") (pinfunction "2_2") (pintype "passive"))
      (node (ref "R7") (pin "1") (pinfunction "1_1") (pintype "passive"))
      (node (ref "SW1") (pin "C") (pinfunction "C_C") (pintype "passive"))
      (node (ref "U1") (pin "10") (pinfunction "VDD_10") (pintype "power_in"))
      (node (ref "U1") (pin "38") (pinfunction "VDD_38") (pintype "power_in"))
      (node (ref "U1") (pin "61") (pinfunction "VDD_61") (pintype "power_in"))
      (node (ref "U1") (pin "87") (pinfunction "VDD_87") (pintype "power_in"))
      (node (ref "U10") (pin "7") (pinfunction "VDD1_7") (pintype "passive"))
      (node (ref "U12") (pin "1") (pinfunction "OUT_1") (pintype "passive"))
      (node (ref "U3") (pin "1") (pinfunction "VDD1_1") (pintype "passive"))
      (node (ref "X5") (pin "1") (pinfunction "1_1") (pintype "passive"))
    )
    (net (code "3") (name "+5V") (class "Default")
      (node (ref "C19") (pin "2") (pinfunction "2_2") (pintype "passive"))
      (node (ref "C20") (pin "2") (pinfunction "2_2") (pintype "passive"))
      (node (ref "C40") (pin "2") (pinfunction "2_2") (pintype "passive"))
      (node (ref "C9") (pin "2") (pinfunction "2_2") (pintype "passive"))
      (node (ref "C95") (pin "2") (pinfunction "2_2") (pintype "passive"))
      (node (ref "U12") (pin "2") (pinfunction "EN_2") (pintype "passive"))
      (node (ref "U12") (pin "8") (pinfunction "VIN_8") (pintype "passive"))
      (node (ref "U25") (pin "1") (pinfunction "IN_1") (pintype "power_in"))
      (node (ref "U25") (pin "3") (pinfunction "EN_3") (pintype "power_in"))
      (node (ref "U34") (pin "1") (pinfunction "EQ1_1") (pintype "passive"))
      (node (ref "U4") (pin "1") (pinfunction "+Vin_1") (pintype "passive"))
      (node (ref "U5") (pin "1") (pinfunction "+Vin_1") (pintype "passive"))
      (node (ref "U6") (pin "5") (pinfunction "VCC_5") (pintype "power_in"))
      (node (ref "U8") (pin "5") (pinfunction "VCC_5") (pintype "power_in"))
      (node (ref "U9") (pin "3") (pinfunction "OUT_3") (pintype "power_in"))
    )
    (net (code "4") (name "/ACCUM_I") (class "Default")
      (node (ref "U1") (pin "53") (pinfunction "ADC0_SE5/PTB1/LPUART0_TX/LPSPI0_SOUT/TCLK0_53") (pintype "bidirectional"))
    )
    (net (code "5") (name "/ACCUM_ID_I") (class "Default")
      (node (ref "U1") (pin "54") (pinfunction "ADC0_SE4/PTB0/LPUART0_RX/LPSPI0_PCS0/LPTMR0_ALT3/PWT_IN3_54") (pintype "bidirectional"))
    )
    (net (code "6") (name "/ACCUM_V") (class "Default")
      (node (ref "U1") (pin "75") (pinfunction "ADC2_SE9/PTB10/FTM3_CH2/LPI2C0_SDAS_75") (pintype "bidirectional"))
    )
    (net (code "7") (name "/AIDS_FAULT") (class "Default")
      (node (ref "U1") (pin "45") (pinfunction "ADC0_SE13/ACMP2_IN4/PTC15/FTM1_CH3_45") (pintype "bidirectional"))
    )
    (net (code "8") (name "/AIDS_FBC") (class "Default")
      (node (ref "U1") (pin "19") (pinfunction "PTE12/FTM0_FLT3/LPUART2_TX_19") (pintype "bidirectional"))
    )
    (net (code "9") (name "/AIDS_SHDN") (class "Default")
      (node (ref "U1") (pin "7") (pinfunction "PTE13/FTM2_FLT0_7") (pintype "bidirectional"))
    )
    (net (code "10") (name "/CAN0H") (class "Default")
      (node (ref "E3") (pin "2") (pinfunction "2_2") (pintype "passive"))
      (node (ref "J2") (pin "2") (pinfunction "2_2") (pintype "passive"))
      (node (ref "U10") (pin "12") (pinfunction "CANH_12") (pintype "passive"))
      (node (ref "X3") (pin "1") (pinfunction "1_1") (pintype "passive"))
      (node (ref "X4") (pin "1") (pinfunction "1_1") (pintype "passive"))
    )
    (net (code "11") (name "/CAN0L") (class "Default")
      (node (ref "E4") (pin "2") (pinfunction "2_2") (pintype "passive"))
      (node (ref "R49") (pin "1") (pinfunction "1_1") (pintype "passive"))
      (node (ref "U10") (pin "11") (pinfunction "CANL_11") (pintype "passive"))
      (node (ref "X3") (pin "2") (pinfunction "2_2") (pintype "passive"))
      (node (ref "X4") (pin "2") (pinfunction "2_2") (pintype "passive"))
    )
    (net (code "12") (name "/CAN0_RX") (class "Default")
      (node (ref "U1") (pin "30") (pinfunction "ADC0_SE10/ACMP0_IN5/XTAL32/PTC2/FTM0_CH2/CAN0_RX_30") (pintype "bidirectional"))
      (node (ref "U10") (pin "5") (pinfunction "RxD_5") (pintype "passive"))
    )
    (net (code "13") (name "/CAN0_TX") (class "Default")
      (node (ref "U1") (pin "29") (pinfunction "ADC0_SE11/ACMP0_IN4/EXTAL32/PTC3/FTM0_CH3/CAN0_TX_29") (pintype "bidirectional"))
      (node (ref "U10") (pin "6") (pinfunction "TxD_6") (pintype "passive"))
    )
    (net (code "14") (name "/CANCTRL") (class "Default")
      (node (ref "U1") (pin "82") (pinfunction "ADC1_SE13/PTA16/FTM1_CH3/LPSPI1_PCS2_82") (pintype "bidirectional"))
      (node (ref "U10") (pin "4") (pinfunction "Vsen_4") (pintype "passive"))
    )
    (net (code "15") (name "/DCDC_MODE") (class "Default")
      (node (ref "U1") (pin "9") (pinfunction "PTE4/BUSOUT/FTM2_QD_PHB/FTM2_CH2/CAN0_RX/FXIO_D6/EWM_OUT_b_9") (pintype "bidirectional"))
    )
    (net (code "16") (name "/DCDC_PGOOD") (class "Default")
      (node (ref "U1") (pin "20") (pinfunction "PTD17/FTM0_FLT2/LPUART2_RX_20") (pintype "bidirectional"))
    )
    (net (code "17") (name "/ENC_A") (class "Default")
      (node (ref "P10") (pin "1") (pinfunction "1_1") (pintype "passive"))
      (node (ref "R10") (pin "1") (pinfunction "1_1") (pintype "passive"))
      (node (ref "SW1") (pin "A") (pinfunction "A_A") (pintype "passive"))
      (node (ref "U1") (pin "35") (pinfunction "PTD11/FTM2_CH1/FTM2_QD_PHA/LPUART2_CTS_35") (pintype "bidirectional"))
    )
    (net (code "18") (name "/ENC_B") (class "Default")
      (node (ref "P11") (pin "1") (pinfunction "1_1") (pintype "passive"))
      (node (ref "R11") (pin "1") (pinfunction "1_1") (pintype "passive"))
      (node (ref "SW1") (pin "B") (pinfunction "B_B") (pintype "passive"))
      (node (ref "U1") (pin "36") (pinfunction "PTD10/FTM2_CH0/FTM2_QD_PHB_36") (pintype "bidirectional"))
    )
    (net (code "19") (name "/ENC_SW") (class "Default")
      (node (ref "P13") (pin "1") (pinfunction "1_1") (pintype "passive"))
      (node (ref "R13") (pin "1") (pinfunction "1_1") (pintype "passive"))
      (node (ref "SW1") (pin "4") (pinfunction "4_4") (pintype "passive"))
      (node (ref "U1") (pin "34") (pinfunction "PTD12/FTM2_CH2/LPI2C1_HREQ/LPUART2_RTS_34") (pintype "bidirectional"))
    )
    (net (code "20") (name "/EN_CHARGER") (class "Default")
      (node (ref "U1") (pin "1") (pinfunction "PTE16/FTM2_CH7/FXIO_D3/TRGMUX_OUT7_1") (pintype "bidirectional"))
    )
    (net (code "21") (name "/EXTAL") (class "Default")
      (node (ref "C10") (pin "1") (pinfunction "1_1") (pintype "passive"))
      (node (ref "R9") (pin "1") (pinfunction "1_1") (pintype "passive"))
      (node (ref "U1") (pin "15") (pinfunction "EXTAL/PTB7/LPI2C0_SCL_15") (pintype "bidirectional"))
      (node (ref "Z1") (pin "3") (pinfunction "3_3") (pintype "passive"))
    )
    (net (code "22") (name "/I2C1_SCL") (class "Default")
      (node (ref "U1") (pin "41") (pinfunction "ACMP1_IN5/PTD9/LPI2C1_SCL/FTM2_FLT3/FTM1_CH5_41") (pintype "bidirectional"))
    )
    (net (code "23") (name "/I2C1_SDA") (class "Default")
      (node (ref "U1") (pin "42") (pinfunction "PTD8/LPI2C1_SDA/FTM2_FLT2/FTM1_CH4_42") (pintype "bidirectional"))
    )
    (net (code "24") (name "/INVERT_I") (class "Default")
      (node (ref "U1") (pin "39") (pinfunction "ADC0_SE9/ACMP1_IN3/PTC1/FTM0_CH1/FTM1_CH7_39") (pintype "bidirectional"))
    )
    (net (code "25") (name "/INVERT_V") (class "Default")
      (node (ref "U1") (pin "43") (pinfunction "ADC0_SE15/PTC17/FTM1_FLT3/LPI2C1_SCLS_43") (pintype "bidirectional"))
    )
    (net (code "26") (name "/INVSW_FAULT") (class "Default")
      (node (ref "U1") (pin "46") (pinfunction "ADC0_SE12/ACMP2_IN5/PTC14/FTM1_CH2_46") (pintype "bidirectional"))
    )
    (net (code "27") (name "/INVSW_ON") (class "Default")
      (node (ref "U1") (pin "18") (pinfunction "PTE3/FTM0_FLT0/LPUART2_RTS/FTM2_FLT0/TRGMUX_IN6/ACMP2_OUT_18") (pintype "bidirectional"))
    )
    (net (code "28") (name "/INV_PATH_STATE") (class "Default")
      (node (ref "U1") (pin "69") (pinfunction "ADC1_SE6/ACMP1_IN6/PTD4/FTM0_FLT3/FTM3_FLT3_69") (pintype "bidirectional"))
    )
    (net (code "29") (name "/LEDCAN0") (class "Default")
      (node (ref "R50") (pin "2") (pinfunction "2_2") (pintype "passive"))
      (node (ref "U1") (pin "95") (pinfunction "PTC5/FTM2_CH0/RTC_CLKOUT/LPI2C1_HREQ/FTM2_QD_PHB/JTAG_TDI_95") (pintype "bidirectional"))
    )
    (net (code "30") (name "/LED_GR") (class "Default")
      (node (ref "U1") (pin "21") (pinfunction "ACMP2_IN0/PTD16/FTM0_CH1_21") (pintype "bidirectional"))
      (node (ref "U6") (pin "2") (pinfunction "A_2") (pintype "input"))
    )
    (net (code "31") (name "/LED_RD") (class "Default")
      (node (ref "U1") (pin "22") (pinfunction "ACMP2_IN1/PTD15/FTM0_CH0_22") (pintype "bidirectional"))
      (node (ref "U8") (pin "2") (pinfunction "A_2") (pintype "input"))
    )
    (net (code "32") (name "/MAINS_PATH_STATE") (class "Default")
      (node (ref "U1") (pin "70") (pinfunction "ADC1_SE3/PTD3/FTM3_CH5/LPSPI1_PCS0/FXIO_D5/TRGMUX_IN4/NMI_b_70") (pintype "bidirectional"))
    )
    (net (code "33") (name "/OLED+5V") (class "Default")
      (node (ref "C115") (pin "1") (pinfunction "1_1") (pintype "passive"))
      (node (ref "L1") (pin "1") (pinfunction "1_1") (pintype "passive"))
      (node (ref "U2") (pin "5") (pinfunction "VIN_5") (pintype "passive"))
      (node (ref "U34") (pin "6") (pinfunction "CQ1_6") (pintype "passive"))
    )
    (net (code "34") (name "/OLEDP") (class "Default")
      (node (ref "U1") (pin "67") (pinfunction "ADC1_SE8/PTB13/FTM0_CH1/FTM3_FLT1_67") (pintype "bidirectional"))
      (node (ref "U34") (pin "2") (pinfunction "GQ2_2") (pintype "passive"))
    )
    (net (code "35") (name "/OLEDV") (class "Default")
      (node (ref "U1") (pin "31") (pinfunction "PTD7/LPUART2_TX/FTM2_FLT3_31") (pintype "bidirectional"))
      (node (ref "U2") (pin "4") (pinfunction "EN/DITH_4") (pintype "passive"))
    )
    (net (code "36") (name "/OLED_CLK") (class "Default")
      (node (ref "LCD1") (pin "13") (pinfunction "D0_13") (pintype "passive"))
      (node (ref "P7") (pin "1") (pinfunction "1_1") (pintype "passive"))
      (node (ref "R6") (pin "1") (pinfunction "1_1") (pintype "passive"))
      (node (ref "U1") (pin "79") (pinfunction "ADC0_SE0/ACMP0_IN0/PTA0/FTM2_CH1/LPI2C0_SCLS/FXIO_D2/FTM2_QD_PHA/LPUART0_CTS/TRGMUX_OUT3_79") (pintype "bidirectional"))
    )
    (net (code "37") (name "/OLED_CS") (class "Default")
      (node (ref "LCD1") (pin "8") (pinfunction "~{CS}_8") (pintype "passive"))
      (node (ref "P4") (pin "1") (pinfunction "1_1") (pintype "passive"))
      (node (ref "U1") (pin "77") (pinfunction "ADC2_SE11/PTB8/FTM3_CH0_77") (pintype "bidirectional"))
    )
    (net (code "38") (name "/OLED_DC") (class "Default")
      (node (ref "LCD1") (pin "10") (pinfunction "D/~{C}_10") (pintype "passive"))
      (node (ref "P6") (pin "1") (pinfunction "1_1") (pintype "passive"))
      (node (ref "U1") (pin "84") (pinfunction "ADC1_SE11/ACMP0_IN6/PTE6/LPSPI0_PCS2/FTM3_CH7/LPUART1_RTS_84") (pintype "bidirectional"))
    )
    (net (code "39") (name "/OLED_DIN") (class "Default")
      (node (ref "LCD1") (pin "14") (pinfunction "D1_14") (pintype "passive"))
      (node (ref "P8") (pin "1") (pinfunction "1_1") (pintype "passive"))
      (node (ref "R2") (pin "1") (pinfunction "1_1") (pintype "passive"))
      (node (ref "R7") (pin "2") (pinfunction "2_2") (pintype "passive"))
      (node (ref "U1") (pin "78") (pinfunction "ADC0_SE1/ACMP0_IN1/PTA1/FTM1_CH1/LPI2C0_SDAS/FXIO_D3/FTM1_QD_PHA/LPUART0_RTS/TRGMUX_OUT0_78") (pintype "bidirectional"))
    )
    (net (code "40") (name "/OLED_RES") (class "Default")
      (node (ref "LCD1") (pin "9") (pinfunction "~{RES}_9") (pintype "passive"))
      (node (ref "P5") (pin "1") (pinfunction "1_1") (pintype "passive"))
      (node (ref "U1") (pin "83") (pinfunction "ADC1_SE12/PTA15/FTM1_CH2/LPSPI0_PCS3_83") (pintype "bidirectional"))
    )
    (net (code "41") (name "/OUT1") (class "Default")
      (node (ref "U1") (pin "51") (pinfunction "PTC11/FTM3_CH5_51") (pintype "bidirectional"))
    )
    (net (code "42") (name "/OUT2") (class "Default")
      (node (ref "U1") (pin "50") (pinfunction "PTC12/FTM3_CH6/FTM2_CH6_50") (pintype "bidirectional"))
    )
    (net (code "43") (name "/OVED_VCC") (class "Default")
      (node (ref "C3") (pin "1") (pinfunction "1_1") (pintype "passive"))
      (node (ref "C4") (pin "2") (pinfunction "2_2") (pintype "passive"))
      (node (ref "C6") (pin "1") (pinfunction "1_1") (pintype "passive"))
      (node (ref "LCD1") (pin "23") (pinfunction "VCC_23") (pintype "passive"))
      (node (ref "R4") (pin "2") (pinfunction "2_2") (pintype "passive"))
      (node (ref "VD1") (pin "1") (pinfunction "1_1") (pintype "passive"))
    )
    (net (code "44") (name "/PIDS_FAULT") (class "Default")
      (node (ref "U1") (pin "23") (pinfunction "ACMP2_IN2/DAC0_OUT/PTE9/FTM0_CH7/LPUART2_CTS_23") (pintype "bidirectional"))
    )
    (net (code "45") (name "/PIDS_SHDN") (class "Default")
      (node (ref "U1") (pin "2") (pinfunction "PTE15/FTM2_CH6/FXIO_D2/TRGMUX_OUT6_2") (pintype "bidirectional"))
    )
    (net (code "46") (name "/PSRC_I") (class "Default")
      (node (ref "U1") (pin "40") (pinfunction "ADC0_SE8/ACMP1_IN4/PTC0/FTM0_CH0/FTM1_CH6_40") (pintype "bidirectional"))
    )
    (net (code "47") (name "/PSRC_V") (class "Default")
      (node (ref "U1") (pin "68") (pinfunction "ADC1_SE7/PTB12/FTM0_CH0/FTM3_FLT2_68") (pintype "bidirectional"))
    )
    (net (code "48") (name "/PWR24_V") (class "Default")
      (node (ref "U1") (pin "71") (pinfunction "ADC1_SE2/PTD2/FTM3_CH4/LPSPI1_SOUT/FXIO_D4/TRGMUX_IN5_71") (pintype "bidirectional"))
    )
    (net (code "49") (name "/RESET") (class "Default")
      (node (ref "C18") (pin "2") (pinfunction "2_2") (pintype "passive"))
      (node (ref "R17") (pin "1") (pinfunction "1_1") (pintype "passive"))
      (node (ref "U1") (pin "97") (pinfunction "PTA5/TCLK1/JTAG_TRST_b/RESET_b_97") (pintype "bidirectional"))
      (node (ref "X5") (pin "10") (pinfunction "10_10") (pintype "passive"))
    )
    (net (code "50") (name "/RS485A") (class "Default")
      (node (ref "R8") (pin "2") (pinfunction "2_2") (pintype "passive"))
      (node (ref "U3") (pin "12") (pinfunction "A_12") (pintype "passive"))
      (node (ref "X1") (pin "2") (pinfunction "2_2") (pintype "passive"))
      (node (ref "X2") (pin "2") (pinfunction "2_2") (pintype "passive"))
    )
    (net (code "51") (name "/RS485B") (class "Default")
      (node (ref "J1") (pin "1") (pinfunction "1_1") (pintype "passive"))
      (node (ref "U3") (pin "13") (pinfunction "B_13") (pintype "passive"))
      (node (ref "X1") (pin "1") (pinfunction "1_1") (pintype "passive"))
      (node (ref "X2") (pin "1") (pinfunction "1_1") (pintype "passive"))
    )
    (net (code "52") (name "/SPI0_CS") (class "Default")
      (node (ref "U1") (pin "27") (pinfunction "PTB5/FTM0_CH5/LPSPI0_PCS1/TRGMUX_IN0/ACMP1_OUT_27") (pintype "bidirectional"))
    )
    (net (code "53") (name "/SPI0_MISO") (class "Default")
      (node (ref "U1") (pin "47") (pinfunction "ADC0_SE7/PTB3/FTM1_CH1/LPSPI0_SIN/FTM1_QD_PHA/TRGMUX_IN2_47") (pintype "bidirectional"))
    )
    (net (code "54") (name "/SPI0_MOSI") (class "Default")
      (node (ref "U1") (pin "28") (pinfunction "ACMP1_IN2/PTB4/FTM0_CH4/LPSPI0_SOUT/TRGMUX_IN1_28") (pintype "bidirectional"))
    )
    (net (code "55") (name "/SPI0_SCK") (class "Default")
      (node (ref "U1") (pin "48") (pinfunction "ADC0_SE6/PTB2/FTM1_CH0/LPSPI0_SCK/FTM1_QD_PHB/TRGMUX_IN3_48") (pintype "bidirectional"))
    )
    (net (code "56") (name "/SPI1_CS") (class "Default")
      (node (ref "U1") (pin "63") (pinfunction "ADC2_SE3/PTB17/FTM0_CH5/LPSPI1_PCS3_63") (pintype "bidirectional"))
    )
    (net (code "57") (name "/SPI1_MISO") (class "Default")
      (node (ref "U1") (pin "65") (pinfunction "ADC1_SE14/PTB15/FTM0_CH3/LPSPI1_SIN_65") (pintype "bidirectional"))
    )
    (net (code "58") (name "/SPI1_MOSI") (class "Default")
      (node (ref "U1") (pin "64") (pinfunction "ADC1_SE15/PTB16/FTM0_CH4/LPSPI1_SOUT_64") (pintype "bidirectional"))
    )
    (net (code "59") (name "/SPI1_SCK") (class "Default")
      (node (ref "U1") (pin "66") (pinfunction "ADC1_SE9/PTB14/FTM0_CH2/LPSPI1_SCK_66") (pintype "bidirectional"))
    )
    (net (code "60") (name "/SWD_CLK") (class "Default")
      (node (ref "R14") (pin "1") (pinfunction "1_1") (pintype "passive"))
      (node (ref "U1") (pin "96") (pinfunction "ACMP0_IN2/PTC4/FTM1_CH0/RTC_CLKOUT/EWM_IN/FTM1_QD_PHB/JTAG_TCLK/SWD_CLK_96") (pintype "bidirectional"))
      (node (ref "X5") (pin "4") (pinfunction "4_4") (pintype "passive"))
    )
    (net (code "61") (name "/SWD_DIO") (class "Default")
      (node (ref "R12") (pin "1") (pinfunction "1_1") (pintype "passive"))
      (node (ref "U1") (pin "98") (pinfunction "PTA4/ACMP0_OUT/EWM_OUT_b/JTAG_TMS/SWD_DIO_98") (pintype "bidirectional"))
      (node (ref "X5") (pin "2") (pinfunction "2_2") (pintype "passive"))
    )
    (net (code "62") (name "/SWO") (class "Default")
      (node (ref "U1") (pin "92") (pinfunction "PTA10/FTM1_CH4/LPUART0_TX/FXIO_D0/JTAG_TDO/noetm_Trace_SWO_92") (pintype "bidirectional"))
      (node (ref "X5") (pin "6") (pinfunction "6_6") (pintype "passive"))
    )
    (net (code "63") (name "/SW_INV_PATH") (class "Default")
      (node (ref "U1") (pin "33") (pinfunction "PTD5/FTM2_CH3/LPTMR0_ALT2/FTM2_FLT1/PWT_IN2/TRGMUX_IN7_33") (pintype "bidirectional"))
    )
    (net (code "64") (name "/SW_MAINS_PATH") (class "Default")
      (node (ref "U1") (pin "32") (pinfunction "PTD6/LPUART2_RX/FTM2_FLT2_32") (pintype "bidirectional"))
    )
    (net (code "65") (name "/UART0_CTS") (class "Default")
      (node (ref "U1") (pin "56") (pinfunction "ADC2_SE14/PTC8/LPUART1_RX/FTM1_FLT0/LPUART0_CTS_56") (pintype "bidirectional"))
      (node (ref "U7") (pin "8") (pinfunction "~{RTS}_8") (pintype "output"))
    )
    (net (code "66") (name "/UART0_RTS") (class "Default")
      (node (ref "U1") (pin "55") (pinfunction "ADC2_SE15/PTC9/LPUART1_TX/FTM1_FLT1/LPUART0_RTS_55") (pintype "bidirectional"))
      (node (ref "U7") (pin "11") (pinfunction "~{CTS}_11") (pintype "input"))
    )
    (net (code "67") (name "/UART0_RX") (class "Default")
      (node (ref "U1") (pin "73") (pinfunction "ADC1_SE0/PTA2/FTM3_CH0/LPI2C0_SDA/EWM_OUT_b/LPUART0_RX_73") (pintype "bidirectional"))
      (node (ref "U7") (pin "7") (pinfunction "TXD_7") (pintype "output"))
    )
    (net (code "68") (name "/UART0_TX") (class "Default")
      (node (ref "U1") (pin "72") (pinfunction "ADC1_SE1/PTA3/FTM3_CH1/LPI2C0_SCL/EWM_IN/LPUART0_TX_72") (pintype "bidirectional"))
      (node (ref "U7") (pin "10") (pinfunction "RXD_10") (pintype "input"))
    )
    (net (code "69") (name "/UART1_RTS") (class "Default")
      (node (ref "U1") (pin "57") (pinfunction "ADC0_SE3/ACMP1_IN1/PTA7/FTM0_FLT2/RTC_CLKIN/LPUART1_RTS_57") (pintype "bidirectional"))
      (node (ref "U3") (pin "5") (pinfunction "DE_5") (pintype "passive"))
    )
    (net (code "70") (name "/UART1_RX") (class "Default")
      (node (ref "U1") (pin "81") (pinfunction "ADC1_SE4/PTC6/LPUART1_RX/CAN1_RX/FTM3_CH2_81") (pintype "bidirectional"))
      (node (ref "U3") (pin "3") (pinfunction "RxD_3") (pintype "passive"))
    )
    (net (code "71") (name "/UART1_TX") (class "Default")
      (node (ref "U1") (pin "80") (pinfunction "ADC1_SE5/PTC7/LPUART1_TX/CAN1_TX/FTM3_CH3_80") (pintype "bidirectional"))
      (node (ref "U3") (pin "6") (pinfunction "TxD_6") (pintype "passive"))
    )
    (net (code "72") (name "/USB_N") (class "Default")
      (node (ref "C34") (pin "1") (pinfunction "1_1") (pintype "passive"))
      (node (ref "R43") (pin "2") (pinfunction "2_2") (pintype "passive"))
      (node (ref "U11") (pin "1") (pinfunction "1_1") (pintype "passive"))
      (node (ref "X19") (pin "2") (pinfunction "D-_2") (pintype "bidirectional"))
    )
    (net (code "73") (name "/USB_P") (class "Default")
      (node (ref "C33") (pin "1") (pinfunction "1_1") (pintype "passive"))
      (node (ref "R42") (pin "2") (pinfunction "2_2") (pintype "passive"))
      (node (ref "U11") (pin "2") (pinfunction "2_2") (pintype "passive"))
      (node (ref "X19") (pin "3") (pinfunction "D+_3") (pintype "bidirectional"))
    )
    (net (code "74") (name "/XTAL") (class "Default")
      (node (ref "C17") (pin "1") (pinfunction "1_1") (pintype "passive"))
      (node (ref "R9") (pin "2") (pinfunction "2_2") (pintype "passive"))
      (node (ref "U1") (pin "16") (pinfunction "XTAL/PTB6/LPI2C0_SDA_16") (pintype "bidirectional"))
      (node (ref "Z1") (pin "1") (pinfunction "1_1") (pintype "passive"))
    )
    (net (code "75") (name "AGND") (class "Default")
      (node (ref "C100") (pin "2") (pinfunction "2_2") (pintype "passive"))
      (node (ref "C11") (pin "1") (pinfunction "1_1") (pintype "passive"))
      (node (ref "C12") (pin "2") (pinfunction "2_2") (pintype "passive"))
      (node (ref "C95") (pin "1") (pinfunction "1_1") (pintype "passive"))
      (node (ref "C96") (pin "1") (pinfunction "1_1") (pintype "passive"))
      (node (ref "C97") (pin "2") (pinfunction "2_2") (pintype "passive"))
      (node (ref "C98") (pin "2") (pinfunction "2_2") (pintype "passive"))
      (node (ref "C99") (pin "2") (pinfunction "2_2") (pintype "passive"))
      (node (ref "L3") (pin "2") (pinfunction "2_2") (pintype "passive"))
      (node (ref "R107") (pin "1") (pinfunction "1_1") (pintype "passive"))
      (node (ref "U1") (pin "13") (pinfunction "VREFL_13") (pintype "power_in"))
      (node (ref "U25") (pin "2") (pinfunction "GND_2") (pintype "power_in"))
      (node (ref "U26") (pin "2") (pinfunction "GND_2") (pintype "power_in"))
    )
    (net (code "76") (name "Earth") (class "Default")
      (node (ref "H1") (pin "0") (pinfunction "0_0") (pintype "passive"))
      (node (ref "VD12") (pin "2") (pinfunction "A_2") (pintype "passive"))
    )
    (net (code "77") (name "GND") (class "Default")
      (node (ref "C1") (pin "1") (pinfunction "1_1") (pintype "passive"))
      (node (ref "C10") (pin "2") (pinfunction "2_2") (pintype "passive"))
      (node (ref "C113") (pin "2") (pinfunction "2_2") (pintype "passive"))
      (node (ref "C114") (pin "2") (pinfunction "2_2") (pintype "passive"))
      (node (ref "C115") (pin "2") (pinfunction "2_2") (pintype "passive"))
      (node (ref "C13") (pin "1") (pinfunction "1_1") (pintype "passive"))
      (node (ref "C14") (pin "1") (pinfunction "1_1") (pintype "passive"))
      (node (ref "C15") (pin "1") (pinfunction "1_1") (pintype "passive"))
      (node (ref "C16") (pin "1") (pinfunction "1_1") (pintype "passive"))
      (node (ref "C17") (pin "2") (pinfunction "2_2") (pintype "passive"))
      (node (ref "C18") (pin "1") (pinfunction "1_1") (pintype "passive"))
      (node (ref "C19") (pin "1") (pinfunction "1_1") (pintype "passive"))
      (node (ref "C2") (pin "2") (pinfunction "2_2") (pintype "passive"))
      (node (ref "C20") (pin "1") (pinfunction "1_1") (pintype "passive"))
      (node (ref "C21") (pin "1") (pinfunction "1_1") (pintype "passive"))
      (node (ref "C22") (pin "1") (pinfunction "1_1") (pintype "passive"))
      (node (ref "C23") (pin "2") (pinfunction "2_2") (pintype "passive"))
      (node (ref "C3") (pin "2") (pinfunction "2_2") (pintype "passive"))
      (node (ref "C30") (pin "2") (pinfunction "2_2") (pintype "passive"))
      (node (ref "C31") (pin "2") (pinfunction "2_2") (pintype "passive"))
      (node (ref "C33") (pin "2") (pinfunction "2_2") (pintype "passive"))
      (node (ref "C34") (pin "2") (pinfunction "2_2") (pintype "passive"))
      (node (ref "C4") (pin "1") (pinfunction "1_1") (pintype "passive"))
      (node (ref "C40") (pin "1") (pinfunction "1_1") (pintype "passive"))
      (node (ref "C45") (pin "2") (pinfunction "2_2") (pintype "passive"))
      (node (ref "C46") (pin "1") (pinfunction "1_1") (pintype "passive"))
      (node (ref "C47") (pin "2") (pinfunction "2_2") (pintype "passive"))
      (node (ref "C48") (pin "1") (pinfunction "1_1") (pintype "passive"))
      (node (ref "C5") (pin "2") (pinfunction "2_2") (pintype "passive"))
      (node (ref "C7") (pin "2") (pinfunction "2_2") (pintype "passive"))
      (node (ref "C9") (pin "1") (pinfunction "1_1") (pintype "passive"))
      (node (ref "L3") (pin "1") (pinfunction "1_1") (pintype "passive"))
      (node (ref "LCD1") (pin "1") (pinfunction "NC_1") (pintype "passive"))
      (node (ref "LCD1") (pin "11") (pinfunction "R/~{W}_11") (pintype "passive"))
      (node (ref "LCD1") (pin "12") (pinfunction "E/~{RD}_12") (pintype "passive"))
      (node (ref "LCD1") (pin "16") (pinfunction "D3_16") (pintype "passive"))
      (node (ref "LCD1") (pin "17") (pinfunction "D4_17") (pintype "passive"))
      (node (ref "LCD1") (pin "18") (pinfunction "D5_18") (pintype "passive"))
      (node (ref "LCD1") (pin "19") (pinfunction "D6_19") (pintype "passive"))
      (node (ref "LCD1") (pin "2") (pinfunction "VLSS_2") (pintype "passive"))
      (node (ref "LCD1") (pin "20") (pinfunction "D7_20") (pintype "passive"))
      (node (ref "LCD1") (pin "24") (pinfunction "NC_24") (pintype "passive"))
      (node (ref "LCD1") (pin "3") (pinfunction "VSS_3") (pintype "passive"))
      (node (ref "LCD1") (pin "6") (pinfunction "BS1_6") (pintype "passive"))
      (node (ref "LCD1") (pin "7") (pinfunction "BS2_7") (pintype "passive"))
      (node (ref "LED17") (pin "2") (pinfunction "2_2") (pintype "passive"))
      (node (ref "P16") (pin "1") (pinfunction "1_1") (pintype "passive"))
      (node (ref "P9") (pin "1") (pinfunction "1_1") (pintype "passive"))
      (node (ref "R10") (pin "2") (pinfunction "2_2") (pintype "passive"))
      (node (ref "R11") (pin "2") (pinfunction "2_2") (pintype "passive"))
      (node (ref "R116") (pin "1") (pinfunction "1_1") (pintype "passive"))
      (node (ref "R117") (pin "1") (pinfunction "1_1") (pintype "passive"))
      (node (ref "R14") (pin "2") (pinfunction "2_2") (pintype "passive"))
      (node (ref "R3") (pin "1") (pinfunction "1_1") (pintype "passive"))
      (node (ref "R5") (pin "2") (pinfunction "2_2") (pintype "passive"))
      (node (ref "SW1") (pin "1") (pinfunction "1_1") (pintype "passive"))
      (node (ref "U1") (pin "14") (pinfunction "VSS_14") (pintype "power_in"))
      (node (ref "U1") (pin "37") (pinfunction "VSS_37") (pintype "power_in"))
      (node (ref "U1") (pin "60") (pinfunction "VSS_60") (pintype "power_in"))
      (node (ref "U1") (pin "86") (pinfunction "VSS_86") (pintype "power_in"))
      (node (ref "U10") (pin "2") (pinfunction "GND1_2") (pintype "passive"))
      (node (ref "U10") (pin "3") (pinfunction "GND1_3") (pintype "passive"))
      (node (ref "U10") (pin "8") (pinfunction "GND1_8") (pintype "passive"))
      (node (ref "U11") (pin "7") (pinfunction "7_7") (pintype "passive"))
      (node (ref "U12") (pin "4") (pinfunction "GND_4") (pintype "passive"))
      (node (ref "U12") (pin "9") (pinfunction "EP_9") (pintype "passive"))
      (node (ref "U2") (pin "2") (pinfunction "GND_2") (pintype "passive"))
      (node (ref "U3") (pin "2") (pinfunction "GND1_2") (pintype "passive"))
      (node (ref "U3") (pin "4") (pinfunction "~{RE}_4") (pintype "passive"))
      (node (ref "U3") (pin "8") (pinfunction "GND1_8") (pintype "passive"))
      (node (ref "U34") (pin "4") (pinfunction "SQ2_4") (pintype "passive"))
      (node (ref "U4") (pin "2") (pinfunction "-Vin_2") (pintype "passive"))
      (node (ref "U5") (pin "2") (pinfunction "-Vin_2") (pintype "passive"))
      (node (ref "U6") (pin "3") (pinfunction "GND_3") (pintype "power_in"))
      (node (ref "U7") (pin "13") (pinfunction "GND_13") (pintype "power_in"))
      (node (ref "U7") (pin "5") (pinfunction "GND_5") (pintype "power_in"))
      (node (ref "U8") (pin "3") (pinfunction "GND_3") (pintype "power_in"))
      (node (ref "U9") (pin "2") (pinfunction "GND_2") (pintype "power_in"))
      (node (ref "VD12") (pin "1") (pinfunction "C_1") (pintype "passive"))
      (node (ref "VD2") (pin "2") (pinfunction "2_2") (pintype "passive"))
      (node (ref "X19") (pin "5") (pinfunction "GND_5") (pintype "power_in"))
      (node (ref "X19") (pin "G1") (pinfunction "CASE_G1") (pintype "power_in"))
      (node (ref "X5") (pin "3") (pinfunction "3_3") (pintype "passive"))
      (node (ref "X5") (pin "5") (pinfunction "5_5") (pintype "passive"))
      (node (ref "Z1") (pin "2") (pinfunction "2_2") (pintype "passive"))
      (node (ref "Z1") (pin "4") (pinfunction "4_4") (pintype "passive"))
    )
    (net (code "78") (name "IGND") (class "Default")
      (node (ref "C114") (pin "1") (pinfunction "1_1") (pintype "passive"))
      (node (ref "C35") (pin "1") (pinfunction "1_1") (pintype "passive"))
      (node (ref "C41") (pin "1") (pinfunction "1_1") (pintype "passive"))
      (node (ref "C42") (pin "1") (pinfunction "1_1") (pintype "passive"))
      (node (ref "E3") (pin "1") (pinfunction "1_1") (pintype "passive"))
      (node (ref "E4") (pin "1") (pinfunction "1_1") (pintype "passive"))
      (node (ref "R117") (pin "2") (pinfunction "2_2") (pintype "passive"))
      (node (ref "U10") (pin "16") (pinfunction "GND2_16") (pintype "passive"))
      (node (ref "U10") (pin "9") (pinfunction "GND2_9") (pintype "passive"))
      (node (ref "U5") (pin "5") (pinfunction "-Vout_5") (pintype "passive"))
      (node (ref "X3") (pin "3") (pinfunction "3_3") (pintype "passive"))
      (node (ref "X4") (pin "3") (pinfunction "3_3") (pintype "passive"))
    )
    (net (code "79") (name "IGND2") (class "Default")
      (node (ref "C113") (pin "1") (pinfunction "1_1") (pintype "passive"))
      (node (ref "C8") (pin "1") (pinfunction "1_1") (pintype "passive"))
      (node (ref "R116") (pin "2") (pinfunction "2_2") (pintype "passive"))
      (node (ref "U3") (pin "15") (pinfunction "GND2_15") (pintype "passive"))
      (node (ref "U3") (pin "9") (pinfunction "GND2_9") (pintype "passive"))
      (node (ref "U4") (pin "5") (pinfunction "-Vout_5") (pintype "passive"))
      (node (ref "X1") (pin "3") (pinfunction "3_3") (pintype "passive"))
      (node (ref "X2") (pin "3") (pinfunction "3_3") (pintype "passive"))
    )
    (net (code "80") (name "IV5V") (class "Default")
      (node (ref "C35") (pin "2") (pinfunction "2_2") (pintype "passive"))
      (node (ref "C41") (pin "2") (pinfunction "2_2") (pintype "passive"))
      (node (ref "C42") (pin "2") (pinfunction "2_2") (pintype "passive"))
      (node (ref "U10") (pin "13") (pinfunction "VDD2_13") (pintype "passive"))
      (node (ref "U5") (pin "7") (pinfunction "+Vout_7") (pintype "passive"))
    )
    (net (code "81") (name "IV5V2") (class "Default")
      (node (ref "C8") (pin "2") (pinfunction "2_2") (pintype "passive"))
      (node (ref "U3") (pin "16") (pinfunction "VDD2_16") (pintype "passive"))
      (node (ref "U4") (pin "7") (pinfunction "+Vout_7") (pintype "passive"))
    )
    (net (code "82") (name "Net-(J1-Pad2)") (class "Default")
      (node (ref "J1") (pin "2") (pinfunction "2_2") (pintype "passive"))
      (node (ref "R8") (pin "1") (pinfunction "1_1") (pintype "passive"))
    )
    (net (code "83") (name "Net-(J2-Pad1)") (class "Default")
      (node (ref "J2") (pin "1") (pinfunction "1_1") (pintype "passive"))
      (node (ref "R49") (pin "2") (pinfunction "2_2") (pintype "passive"))
    )
    (net (code "84") (name "Net-(LCD1-D2)") (class "Default")
      (node (ref "LCD1") (pin "15") (pinfunction "D2_15") (pintype "passive"))
      (node (ref "R2") (pin "2") (pinfunction "2_2") (pintype "passive"))
    )
    (net (code "85") (name "Net-(LCD1-IREF)") (class "Default")
      (node (ref "LCD1") (pin "21") (pinfunction "IREF_21") (pintype "passive"))
      (node (ref "P2") (pin "1") (pinfunction "1_1") (pintype "passive"))
      (node (ref "R3") (pin "2") (pinfunction "2_2") (pintype "passive"))
    )
    (net (code "86") (name "Net-(LCD1-VH)") (class "Default")
      (node (ref "C5") (pin "1") (pinfunction "1_1") (pintype "passive"))
      (node (ref "LCD1") (pin "22") (pinfunction "VH_22") (pintype "passive"))
      (node (ref "P3") (pin "1") (pinfunction "1_1") (pintype "passive"))
    )
    (net (code "87") (name "Net-(LED13-Pad2)") (class "Default")
      (node (ref "LED13") (pin "2") (pinfunction "2_2") (pintype "passive"))
      (node (ref "R38") (pin "1") (pinfunction "1_1") (pintype "passive"))
    )
    (net (code "88") (name "Net-(LED17-Pad1)") (class "Default")
      (node (ref "LED17") (pin "1") (pinfunction "1_1") (pintype "passive"))
      (node (ref "R50") (pin "1") (pinfunction "1_1") (pintype "passive"))
    )
    (net (code "89") (name "Net-(P14-Pad1)") (class "Default")
      (node (ref "P14") (pin "1") (pinfunction "1_1") (pintype "passive"))
      (node (ref "R16") (pin "2") (pinfunction "2_2") (pintype "passive"))
      (node (ref "SW1") (pin "3") (pinfunction "3_3") (pintype "passive"))
    )
    (net (code "90") (name "Net-(P15-Pad1)") (class "Default")
      (node (ref "P15") (pin "1") (pinfunction "1_1") (pintype "passive"))
      (node (ref "R15") (pin "2") (pinfunction "2_2") (pintype "passive"))
      (node (ref "SW1") (pin "2") (pinfunction "2_2") (pintype "passive"))
    )
    (net (code "91") (name "Net-(U2-FB)") (class "Default")
      (node (ref "C6") (pin "2") (pinfunction "2_2") (pintype "passive"))
      (node (ref "R4") (pin "1") (pinfunction "1_1") (pintype "passive"))
      (node (ref "R5") (pin "1") (pinfunction "1_1") (pintype "passive"))
      (node (ref "U2") (pin "3") (pinfunction "FB_3") (pintype "passive"))
    )
    (net (code "92") (name "Net-(U2-SW)") (class "Default")
      (node (ref "L1") (pin "2") (pinfunction "2_2") (pintype "passive"))
      (node (ref "U2") (pin "1") (pinfunction "SW_1") (pintype "passive"))
      (node (ref "VD1") (pin "2") (pinfunction "2_2") (pintype "passive"))
    )
    (net (code "93") (name "Net-(U6-Y)") (class "Default")
      (node (ref "R15") (pin "1") (pinfunction "1_1") (pintype "passive"))
      (node (ref "U6") (pin "4") (pinfunction "Y_4") (pintype "open_collector"))
    )
    (net (code "94") (name "Net-(U7-CBUS0)") (class "Default")
      (node (ref "R38") (pin "2") (pinfunction "2_2") (pintype "passive"))
      (node (ref "U7") (pin "6") (pinfunction "CBUS0_6") (pintype "bidirectional"))
    )
    (net (code "95") (name "Net-(U7-USBDM)") (class "Default")
      (node (ref "R43") (pin "1") (pinfunction "1_1") (pintype "passive"))
      (node (ref "U7") (pin "1") (pinfunction "USBDM_1") (pintype "bidirectional"))
    )
    (net (code "96") (name "Net-(U7-USBDP)") (class "Default")
      (node (ref "R42") (pin "1") (pinfunction "1_1") (pintype "passive"))
      (node (ref "U7") (pin "12") (pinfunction "USBDP_12") (pintype "bidirectional"))
    )
    (net (code "97") (name "Net-(U7-VCC)") (class "Default")
      (node (ref "C30") (pin "1") (pinfunction "1_1") (pintype "passive"))
      (node (ref "C47") (pin "1") (pinfunction "1_1") (pintype "passive"))
      (node (ref "L4") (pin "2") (pinfunction "2_2") (pintype "passive"))
      (node (ref "U7") (pin "4") (pinfunction "VCC_4") (pintype "power_in"))
    )
    (net (code "98") (name "Net-(U8-Y)") (class "Default")
      (node (ref "R16") (pin "1") (pinfunction "1_1") (pintype "passive"))
      (node (ref "U8") (pin "4") (pinfunction "Y_4") (pintype "open_collector"))
    )
    (net (code "99") (name "Net-(U26-IN+)") (class "Default")
      (node (ref "C98") (pin "1") (pinfunction "1_1") (pintype "passive"))
      (node (ref "R106") (pin "1") (pinfunction "1_1") (pintype "passive"))
      (node (ref "R107") (pin "2") (pinfunction "2_2") (pintype "passive"))
      (node (ref "U26") (pin "3") (pinfunction "IN+_3") (pintype "passive"))
    )
    (net (code "100") (name "Net-(U26-IN-)") (class "Default")
      (node (ref "R108") (pin "2") (pinfunction "2_2") (pintype "passive"))
      (node (ref "U26") (pin "1") (pinfunction "OUT_1") (pintype "passive"))
      (node (ref "U26") (pin "4") (pinfunction "IN-_4") (pintype "passive"))
    )
    (net (code "101") (name "Net-(U34-BQ1)") (class "Default")
      (node (ref "U34") (pin "3") (pinfunction "DQ2_3") (pintype "passive"))
      (node (ref "U34") (pin "5") (pinfunction "BQ1_5") (pintype "passive"))
    )
    (net (code "102") (name "Net-(X19-ID)") (class "Default")
      (node (ref "U11") (pin "3") (pinfunction "3_3") (pintype "passive"))
      (node (ref "X19") (pin "4") (pinfunction "ID_4") (pintype "passive"))
    )
    (net (code "103") (name "Net-(X19-VBUS)") (class "Default")
      (node (ref "C45") (pin "1") (pinfunction "1_1") (pintype "passive"))
      (node (ref "L4") (pin "1") (pinfunction "1_1") (pintype "passive"))
      (node (ref "U11") (pin "6") (pinfunction "6_6") (pintype "passive"))
      (node (ref "X19") (pin "1") (pinfunction "VBUS_1") (pintype "power_in"))
    )
    (net (code "104") (name "PWR24F") (class "Default")
      (node (ref "C23") (pin "1") (pinfunction "1_1") (pintype "passive"))
      (node (ref "F1") (pin "2") (pinfunction "2_2") (pintype "passive"))
      (node (ref "U9") (pin "1") (pinfunction "IN_1") (pintype "power_in"))
      (node (ref "VD2") (pin "1") (pinfunction "1_1") (pintype "passive"))
    )
    (net (code "105") (name "SYS_PWR") (class "Default")
      (node (ref "F1") (pin "1") (pinfunction "1_1") (pintype "passive"))
    )
    (net (code "106") (name "VCCIO") (class "Default")
      (node (ref "C31") (pin "1") (pinfunction "1_1") (pintype "passive"))
      (node (ref "LED13") (pin "1") (pinfunction "1_1") (pintype "passive"))
      (node (ref "U7") (pin "2") (pinfunction "~{RESET}_2") (pintype "input"))
      (node (ref "U7") (pin "3") (pinfunction "3V3OUT_3") (pintype "power_in"))
      (node (ref "U7") (pin "9") (pinfunction "VCCIO_9") (pintype "power_in"))
    )
    (net (code "107") (name "VREF_1.65V") (class "Default")
      (node (ref "C99") (pin "1") (pinfunction "1_1") (pintype "passive"))
      (node (ref "R108") (pin "1") (pinfunction "1_1") (pintype "passive"))
      (node (ref "U1") (pin "3") (pinfunction "ADC2_SE1/PTD1/FTM0_CH3/LPSPI1_SIN/FTM2_CH1/FXIO_D1/TRGMUX_OUT2_3") (pintype "bidirectional"))
    )
    (net (code "108") (name "unconnected-(H2-Pad0)") (class "Default")
      (node (ref "H2") (pin "0") (pinfunction "0_0") (pintype "passive"))
    )
    (net (code "109") (name "unconnected-(H3-Pad0)") (class "Default")
      (node (ref "H3") (pin "0") (pinfunction "0_0") (pintype "passive"))
    )
    (net (code "110") (name "unconnected-(H4-Pad0)") (class "Default")
      (node (ref "H4") (pin "0") (pinfunction "0_0") (pintype "passive"))
    )
    (net (code "111") (name "unconnected-(LCD1-NC-Pad4)") (class "Default")
      (node (ref "LCD1") (pin "4") (pinfunction "NC_4") (pintype "passive"))
    )
    (net (code "112") (name "unconnected-(U1-ACMP0_IN3{slash}PTE8{slash}FTM0_CH6-Pad26)") (class "Default")
      (node (ref "U1") (pin "26") (pinfunction "ACMP0_IN3/PTE8/FTM0_CH6_26") (pintype "bidirectional"))
    )
    (net (code "113") (name "unconnected-(U1-ACMP2_IN3{slash}PTE14{slash}FTM0_FLT1{slash}FTM2_FLT1-Pad17)") (class "Default")
      (node (ref "U1") (pin "17") (pinfunction "ACMP2_IN3/PTE14/FTM0_FLT1/FTM2_FLT1_17") (pintype "bidirectional"))
    )
    (net (code "114") (name "unconnected-(U1-ADC0_SE2{slash}ACMP1_IN0{slash}PTA6{slash}FTM0_FLT1{slash}LPSPI1_PCS1{slash}LPUART1_CTS-Pad58)") (class "Default")
      (node (ref "U1") (pin "58") (pinfunction "ADC0_SE2/ACMP1_IN0/PTA6/FTM0_FLT1/LPSPI1_PCS1/LPUART1_CTS_58") (pintype "bidirectional"))
    )
    (net (code "115") (name "unconnected-(U1-ADC0_SE14{slash}PTC16{slash}FTM1_FLT2{slash}LPI2C1_SDAS-Pad44)") (class "Default")
      (node (ref "U1") (pin "44") (pinfunction "ADC0_SE14/PTC16/FTM1_FLT2/LPI2C1_SDAS_44") (pintype "bidirectional"))
    )
    (net (code "116") (name "unconnected-(U1-ADC1_SE10{slash}PTE2{slash}LPSPI0_SOUT{slash}LPTMR0_ALT3{slash}FTM3_CH6{slash}PWT_IN3{slash}LPUART1_CTS-Pad85)") (class "Default")
      (node (ref "U1") (pin "85") (pinfunction "ADC1_SE10/PTE2/LPSPI0_SOUT/LPTMR0_ALT3/FTM3_CH6/PWT_IN3/LPUART1_CTS_85") (pintype "bidirectional"))
    )
    (net (code "117") (name "unconnected-(U1-ADC2_SE0{slash}PTD0{slash}FTM0_CH2{slash}LPSPI1_SCK{slash}FTM2_CH0{slash}FXIO_D0{slash}TRGMUX_OUT1-Pad4)") (class "Default")
      (node (ref "U1") (pin "4") (pinfunction "ADC2_SE0/PTD0/FTM0_CH2/LPSPI1_SCK/FTM2_CH0/FXIO_D0/TRGMUX_OUT1_4") (pintype "bidirectional"))
    )
    (net (code "118") (name "unconnected-(U1-ADC2_SE2{slash}ACMP2_IN6{slash}PTE7{slash}FTM0_CH7{slash}FTM3_FLT0-Pad59)") (class "Default")
      (node (ref "U1") (pin "59") (pinfunction "ADC2_SE2/ACMP2_IN6/PTE7/FTM0_CH7/FTM3_FLT0_59") (pintype "bidirectional"))
    )
    (net (code "119") (name "unconnected-(U1-ADC2_SE4{slash}PTA13{slash}FTM1_CH7{slash}CAN1_TX{slash}LPI2C1_SCLS-Pad89)") (class "Default")
      (node (ref "U1") (pin "89") (pinfunction "ADC2_SE4/PTA13/FTM1_CH7/CAN1_TX/LPI2C1_SCLS_89") (pintype "bidirectional"))
    )
    (net (code "120") (name "unconnected-(U1-ADC2_SE5{slash}PTA12{slash}FTM1_CH6{slash}CAN1_RX{slash}LPI2C1_SDAS-Pad90)") (class "Default")
      (node (ref "U1") (pin "90") (pinfunction "ADC2_SE5/PTA12/FTM1_CH6/CAN1_RX/LPI2C1_SDAS_90") (pintype "bidirectional"))
    )
    (net (code "121") (name "unconnected-(U1-ADC2_SE6{slash}PTE1{slash}LPSPI0_SIN{slash}LPI2C0_HREQ{slash}LPI2C1_SCL{slash}FTM1_FLT1-Pad93)") (class "Default")
      (node (ref "U1") (pin "93") (pinfunction "ADC2_SE6/PTE1/LPSPI0_SIN/LPI2C0_HREQ/LPI2C1_SCL/FTM1_FLT1_93") (pintype "bidirectional"))
    )
    (net (code "122") (name "unconnected-(U1-ADC2_SE7{slash}PTE0{slash}LPSPI0_SCK{slash}TCLK1{slash}LPI2C1_SDA{slash}FTM1_FLT2-Pad94)") (class "Default")
      (node (ref "U1") (pin "94") (pinfunction "ADC2_SE7/PTE0/LPSPI0_SCK/TCLK1/LPI2C1_SDA/FTM1_FLT2_94") (pintype "bidirectional"))
    )
    (net (code "123") (name "unconnected-(U1-ADC2_SE8{slash}PTB11{slash}FTM3_CH3{slash}LPI2C0_HREQ-Pad74)") (class "Default")
      (node (ref "U1") (pin "74") (pinfunction "ADC2_SE8/PTB11/FTM3_CH3/LPI2C0_HREQ_74") (pintype "bidirectional"))
    )
    (net (code "124") (name "unconnected-(U1-ADC2_SE10{slash}PTB9{slash}FTM3_CH1{slash}LPI2C0_SCLS-Pad76)") (class "Default")
      (node (ref "U1") (pin "76") (pinfunction "ADC2_SE10/PTB9/FTM3_CH1/LPI2C0_SCLS_76") (pintype "bidirectional"))
    )
    (net (code "125") (name "unconnected-(U1-ADC2_SE12{slash}PTE10{slash}CLKOUT{slash}FTM2_CH4{slash}FXIO_D4{slash}TRGMUX_OUT4-Pad6)") (class "Default")
      (node (ref "U1") (pin "6") (pinfunction "ADC2_SE12/PTE10/CLKOUT/FTM2_CH4/FXIO_D4/TRGMUX_OUT4_6") (pintype "bidirectional"))
    )
    (net (code "126") (name "unconnected-(U1-ADC2_SE13{slash}PTE11{slash}PWT_IN1{slash}LPTMR0_ALT1{slash}FTM2_CH5{slash}FXIO_D5{slash}TRGMUX_OUT5-Pad5)") (class "Default")
      (node (ref "U1") (pin "5") (pinfunction "ADC2_SE13/PTE11/PWT_IN1/LPTMR0_ALT1/FTM2_CH5/FXIO_D5/TRGMUX_OUT5_5") (pintype "bidirectional"))
    )
    (net (code "127") (name "unconnected-(U1-PTA8{slash}FXIO_D6{slash}FTM3_FLT3-Pad100)") (class "Default")
      (node (ref "U1") (pin "100") (pinfunction "PTA8/FXIO_D6/FTM3_FLT3_100") (pintype "bidirectional"))
    )
    (net (code "128") (name "unconnected-(U1-PTA9{slash}FXIO_D7{slash}FTM3_FLT2{slash}FTM1_FLT3-Pad99)") (class "Default")
      (node (ref "U1") (pin "99") (pinfunction "PTA9/FXIO_D7/FTM3_FLT2/FTM1_FLT3_99") (pintype "bidirectional"))
    )
    (net (code "129") (name "unconnected-(U1-PTA11{slash}FTM1_CH5{slash}LPUART0_RX{slash}FXIO_D1-Pad91)") (class "Default")
      (node (ref "U1") (pin "91") (pinfunction "PTA11/FTM1_CH5/LPUART0_RX/FXIO_D1_91") (pintype "bidirectional"))
    )
    (net (code "130") (name "unconnected-(U1-PTA14{slash}FTM0_FLT0{slash}FTM3_FLT1{slash}EWM_IN{slash}FTM1_FLT0{slash}BUSOUT-Pad88)") (class "Default")
      (node (ref "U1") (pin "88") (pinfunction "PTA14/FTM0_FLT0/FTM3_FLT1/EWM_IN/FTM1_FLT0/BUSOUT_88") (pintype "bidirectional"))
    )
    (net (code "131") (name "unconnected-(U1-PTA17{slash}FTM0_CH6{slash}FTM3_FLT0{slash}EWM_OUT_b-Pad62)") (class "Default")
      (node (ref "U1") (pin "62") (pinfunction "PTA17/FTM0_CH6/FTM3_FLT0/EWM_OUT_b_62") (pintype "bidirectional"))
    )
    (net (code "132") (name "unconnected-(U1-PTC10{slash}FTM3_CH4-Pad52)") (class "Default")
      (node (ref "U1") (pin "52") (pinfunction "PTC10/FTM3_CH4_52") (pintype "bidirectional"))
    )
    (net (code "133") (name "unconnected-(U1-PTC13{slash}FTM3_CH7{slash}FTM2_CH7-Pad49)") (class "Default")
      (node (ref "U1") (pin "49") (pinfunction "PTC13/FTM3_CH7/FTM2_CH7_49") (pintype "bidirectional"))
    )
    (net (code "134") (name "unconnected-(U1-PTD13{slash}FTM2_CH4{slash}RTC_CLKOUT-Pad25)") (class "Default")
      (node (ref "U1") (pin "25") (pinfunction "PTD13/FTM2_CH4/RTC_CLKOUT_25") (pintype "bidirectional"))
    )
    (net (code "135") (name "unconnected-(U1-PTD14{slash}FTM2_CH5{slash}CLKOUT-Pad24)") (class "Default")
      (node (ref "U1") (pin "24") (pinfunction "PTD14/FTM2_CH5/CLKOUT_24") (pintype "bidirectional"))
    )
    (net (code "136") (name "unconnected-(U1-PTE5{slash}TCLK2{slash}FTM2_QD_PHA{slash}FTM2_CH3{slash}CAN0_TX{slash}FXIO_D7{slash}EWM_IN-Pad8)") (class "Default")
      (node (ref "U1") (pin "8") (pinfunction "PTE5/TCLK2/FTM2_QD_PHA/FTM2_CH3/CAN0_TX/FXIO_D7/EWM_IN_8") (pintype "bidirectional"))
    )
    (net (code "137") (name "unconnected-(U3-NC-Pad10)") (class "Default")
      (node (ref "U3") (pin "10") (pinfunction "NC_10") (pintype "passive"))
    )
    (net (code "138") (name "unconnected-(U3-NC-Pad11)") (class "Default")
      (node (ref "U3") (pin "11") (pinfunction "NC_11") (pintype "passive"))
    )
    (net (code "139") (name "unconnected-(U3-NC-Pad14)") (class "Default")
      (node (ref "U3") (pin "14") (pinfunction "NC_14") (pintype "passive"))
    )
    (net (code "140") (name "unconnected-(U3-PV-Pad7)") (class "Default")
      (node (ref "U3") (pin "7") (pinfunction "PV_7") (pintype "passive"))
    )
    (net (code "141") (name "unconnected-(U10-NC-Pad1)") (class "Default")
      (node (ref "U10") (pin "1") (pinfunction "NC_1") (pintype "passive"))
    )
    (net (code "142") (name "unconnected-(U10-NC-Pad14)") (class "Default")
      (node (ref "U10") (pin "14") (pinfunction "NC_14") (pintype "passive"))
    )
    (net (code "143") (name "unconnected-(U10-NC-Pad15)") (class "Default")
      (node (ref "U10") (pin "15") (pinfunction "NC_15") (pintype "passive"))
    )
    (net (code "144") (name "unconnected-(U10-VREF-Pad10)") (class "Default")
      (node (ref "U10") (pin "10") (pinfunction "VREF_10") (pintype "passive"))
    )
    (net (code "145") (name "unconnected-(X5-Pad7)") (class "Default")
      (node (ref "X5") (pin "7") (pinfunction "7_7") (pintype "passive"))
    )
    (net (code "146") (name "unconnected-(X5-Pad8)") (class "Default")
      (node (ref "X5") (pin "8") (pinfunction "8_8") (pintype "passive"))
    )
    (net (code "147") (name "unconnected-(X5-Pad9)") (class "Default")
      (node (ref "X5") (pin "9") (pinfunction "9_9") (pintype "passive"))
    )
  )
)
